# car.net
KiCad netlist of a schematic drawn in EAGLE
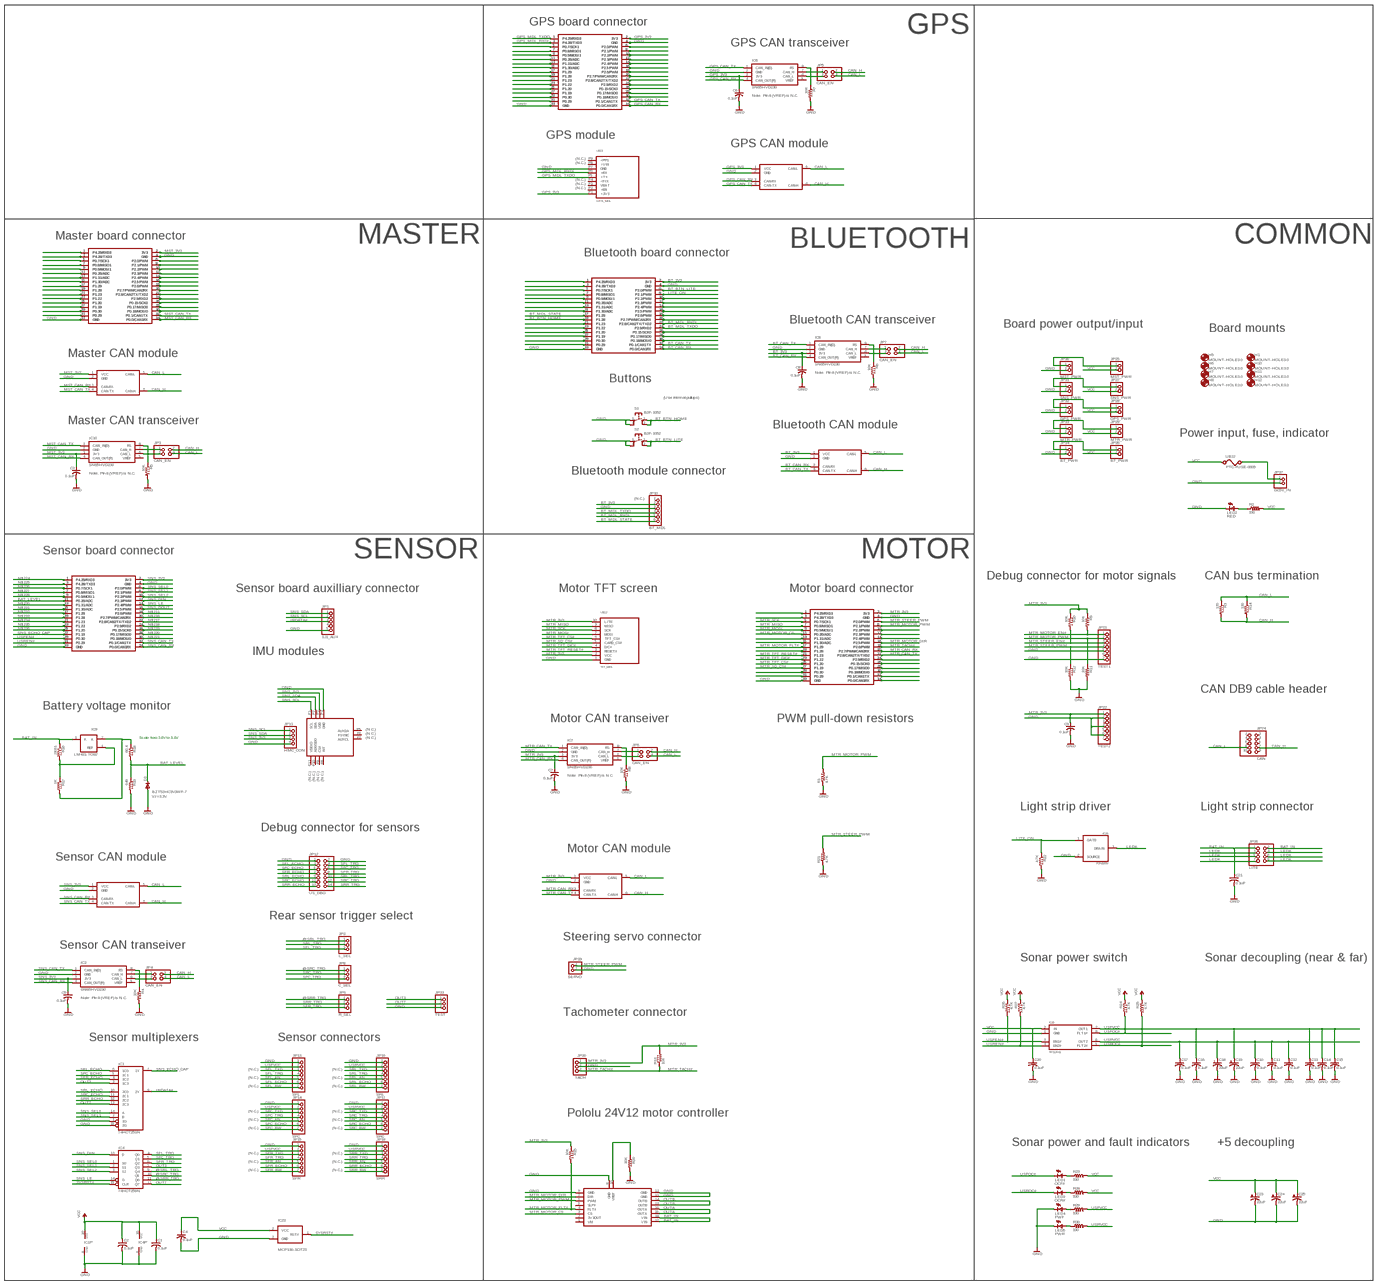
[diagram p0: schematic, sheet 1, overview]
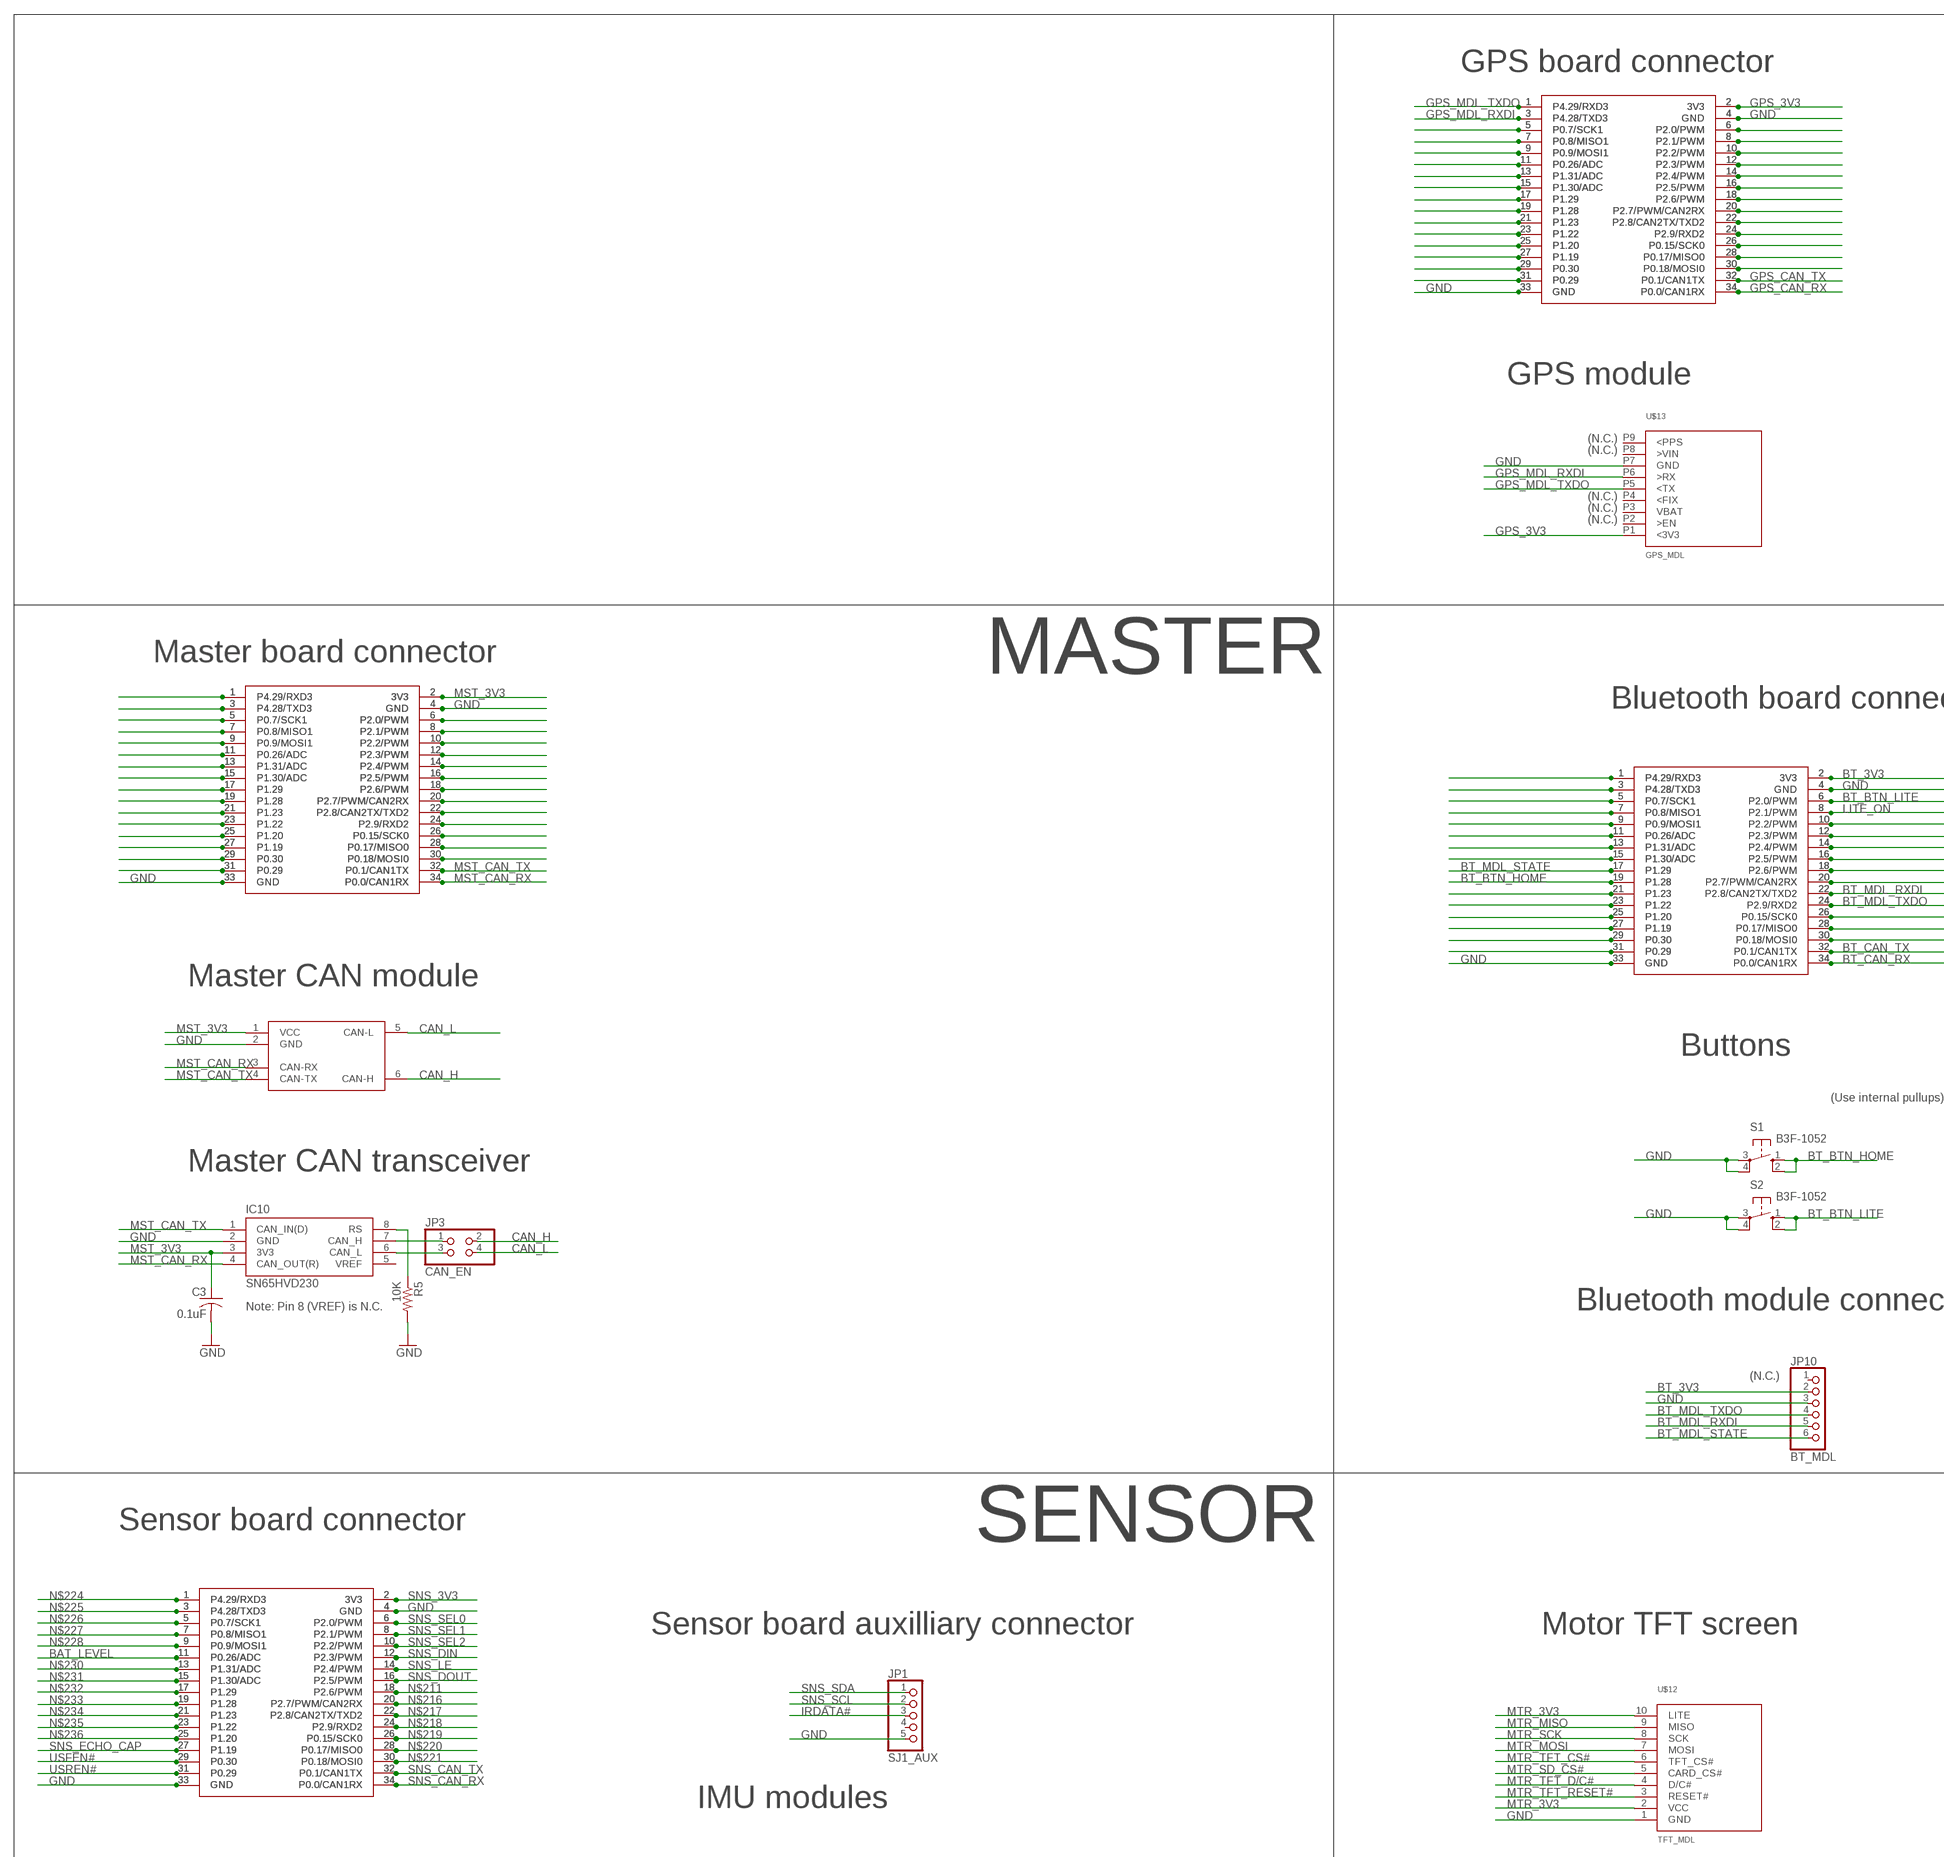
[diagram p1: schematic, sheet 1, part 1 of 4]
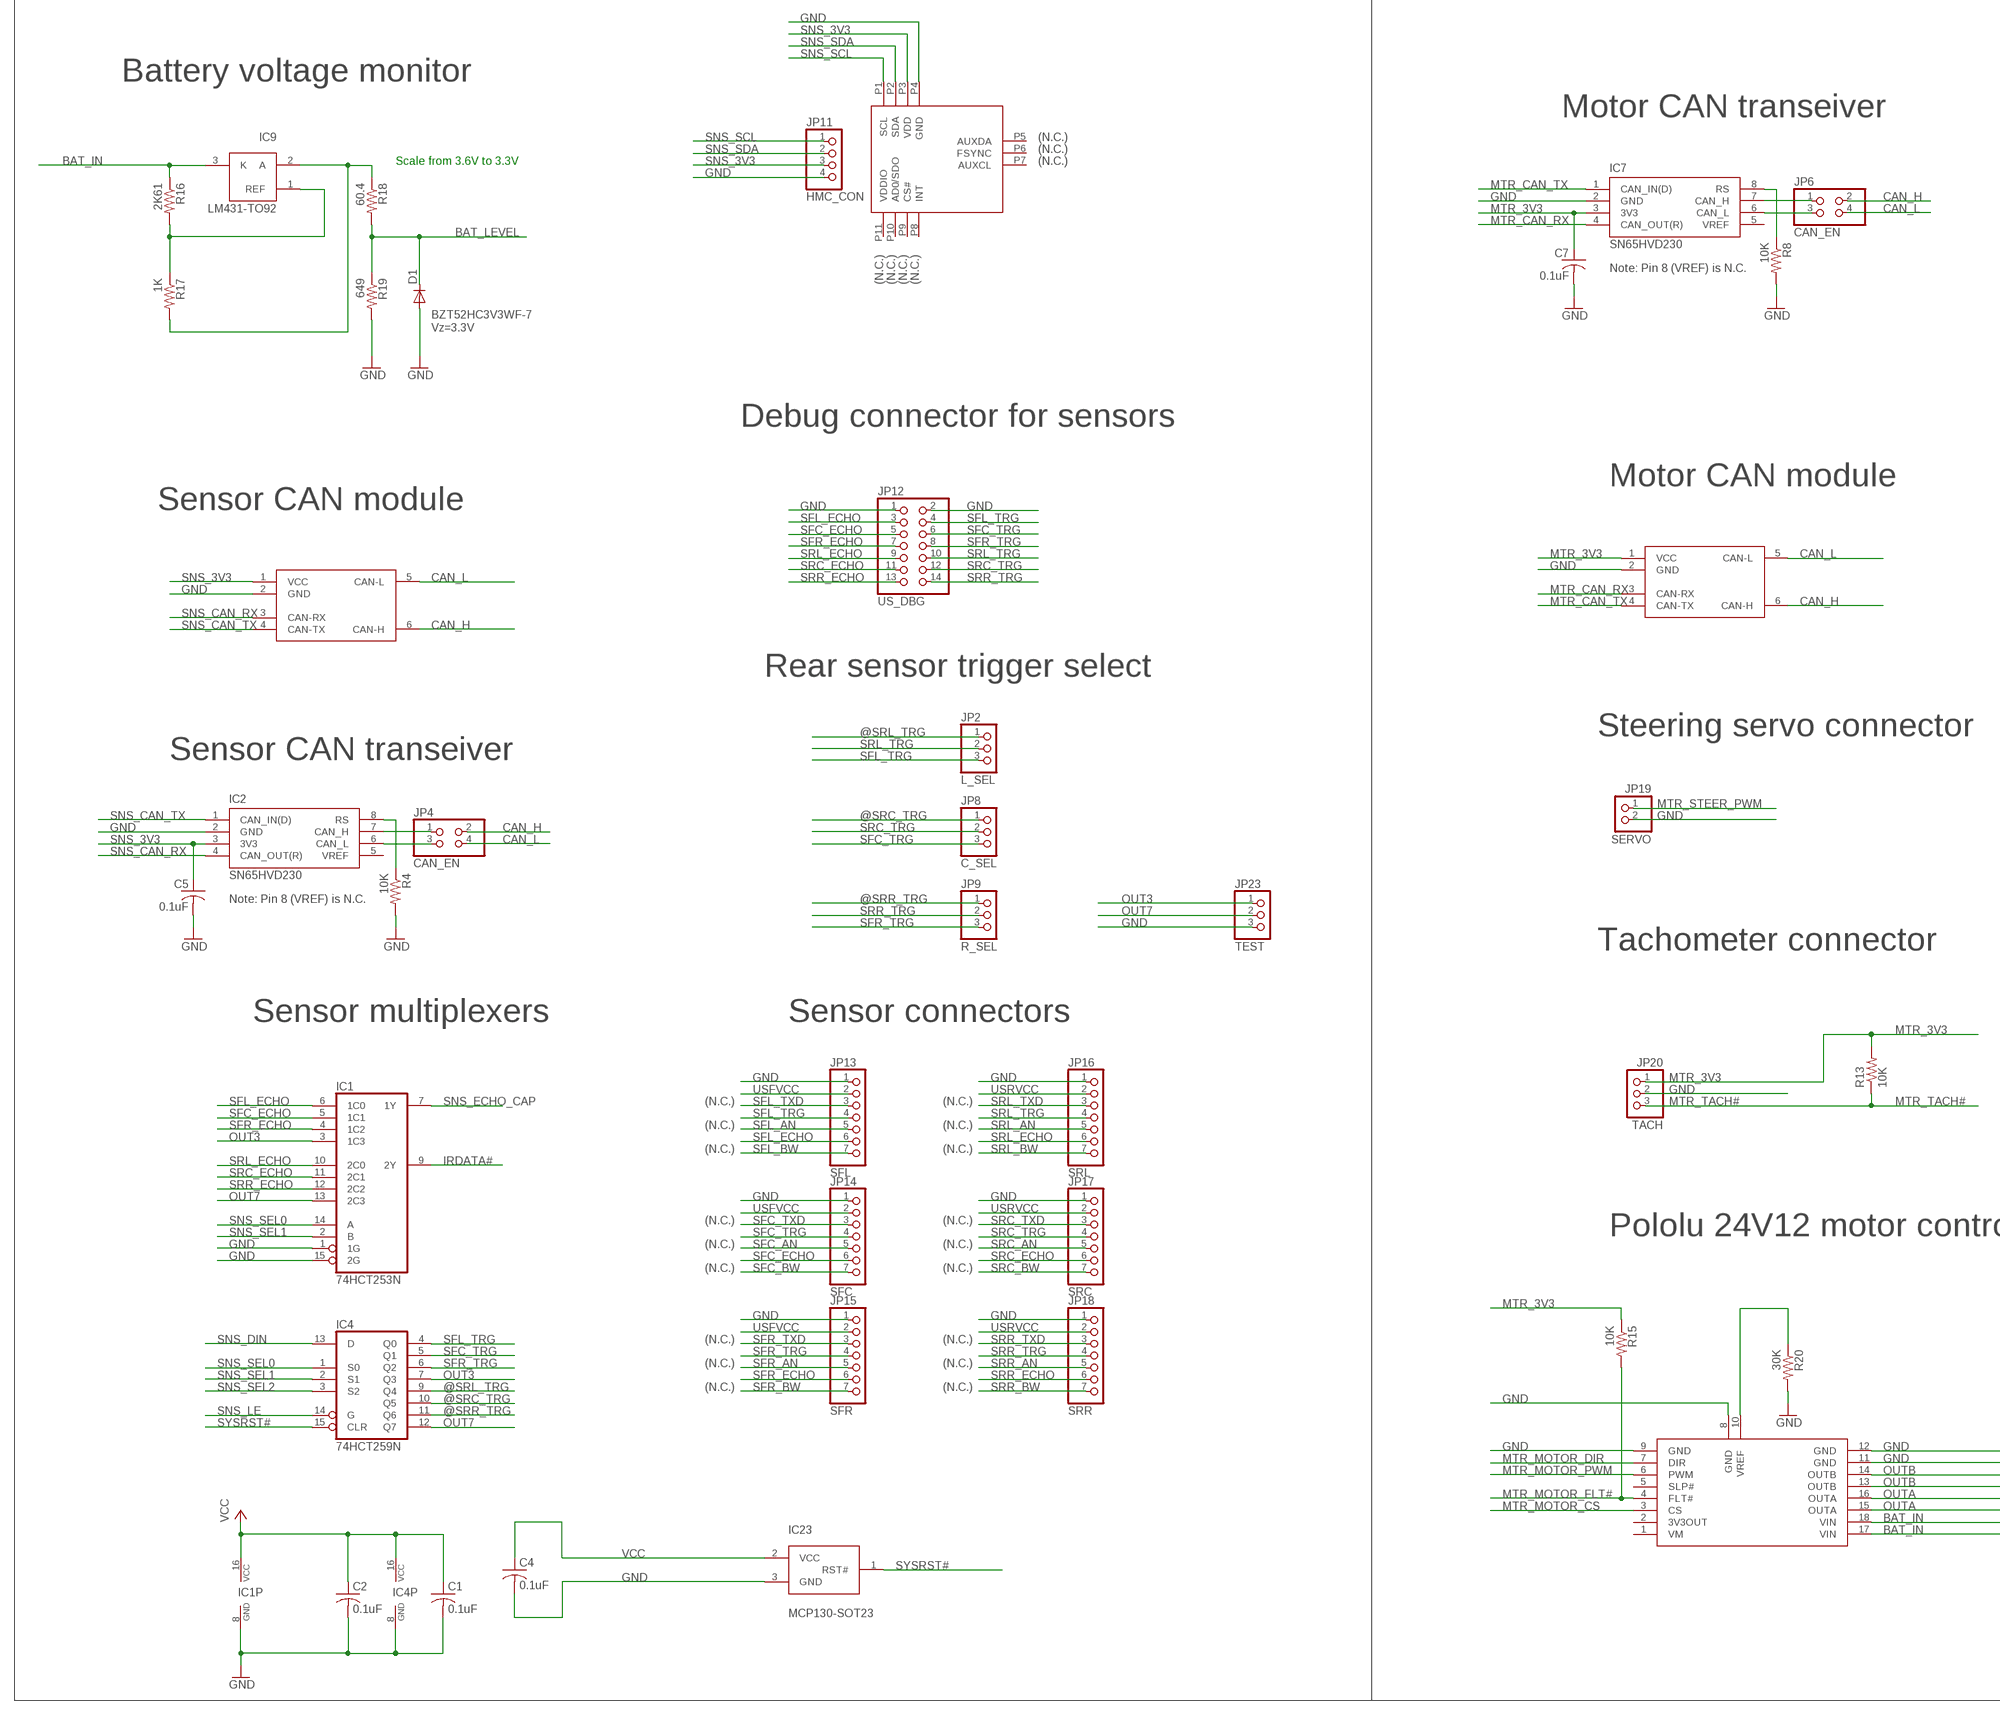
[diagram p2: schematic, sheet 1, part 2 of 4]
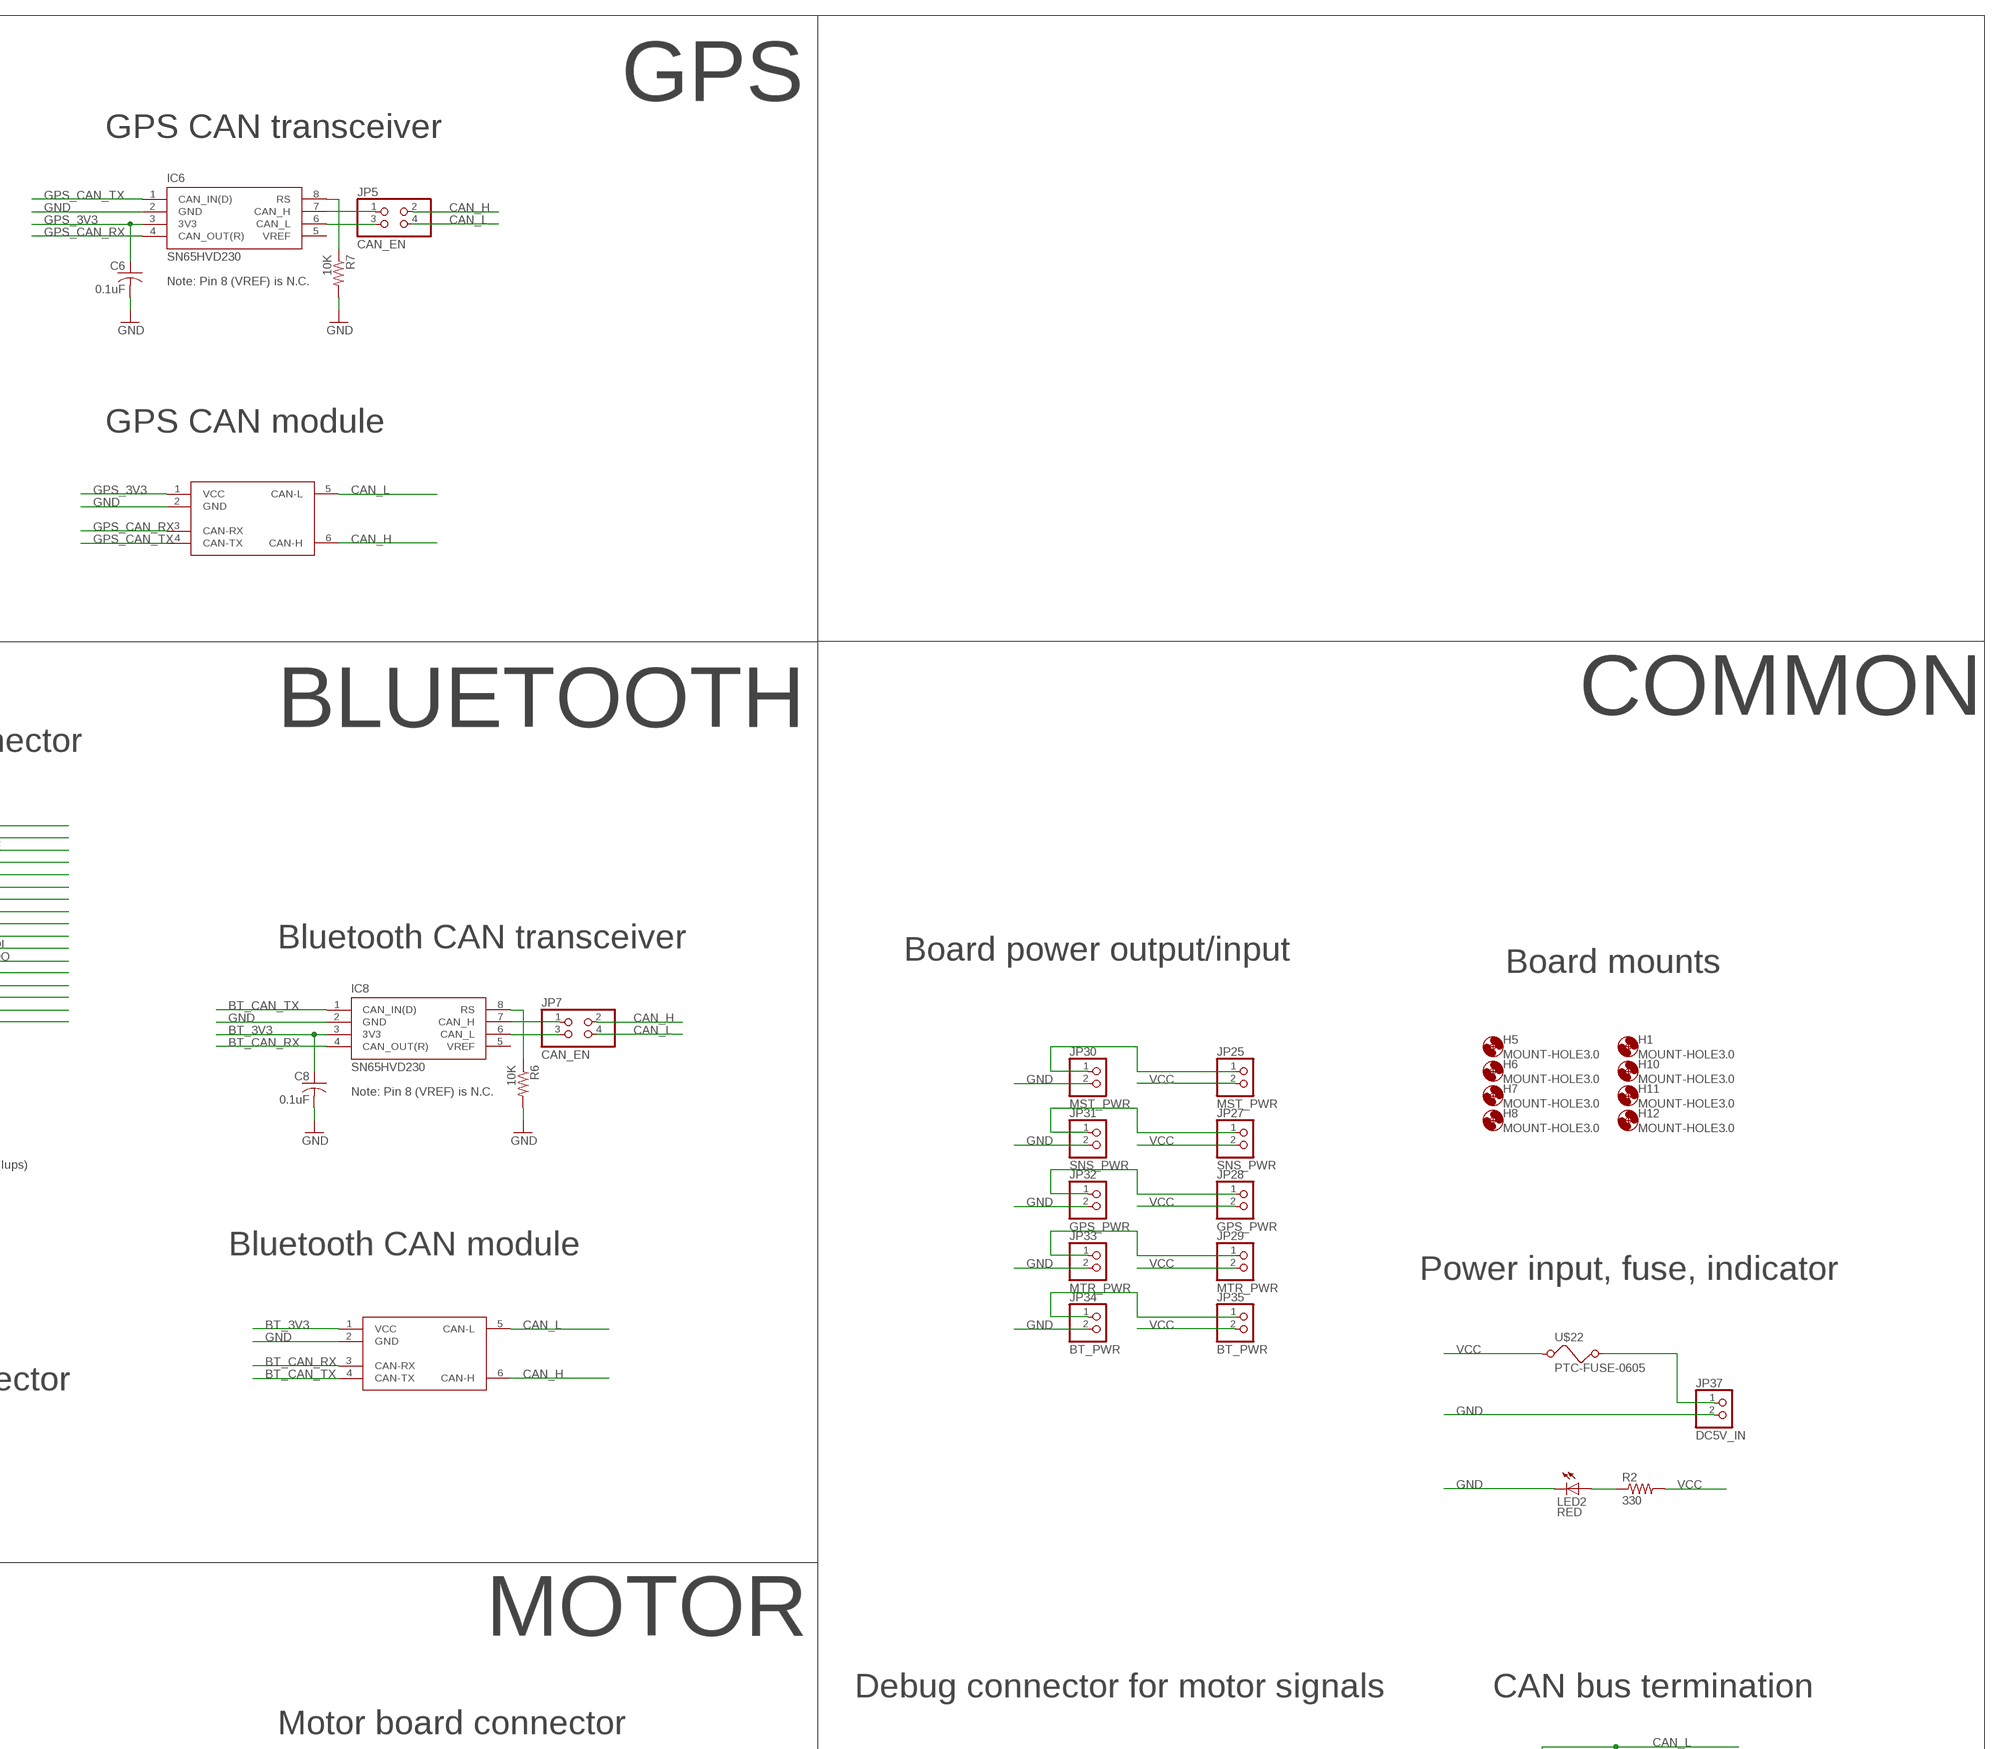
[diagram p3: schematic, sheet 1, part 3 of 4]
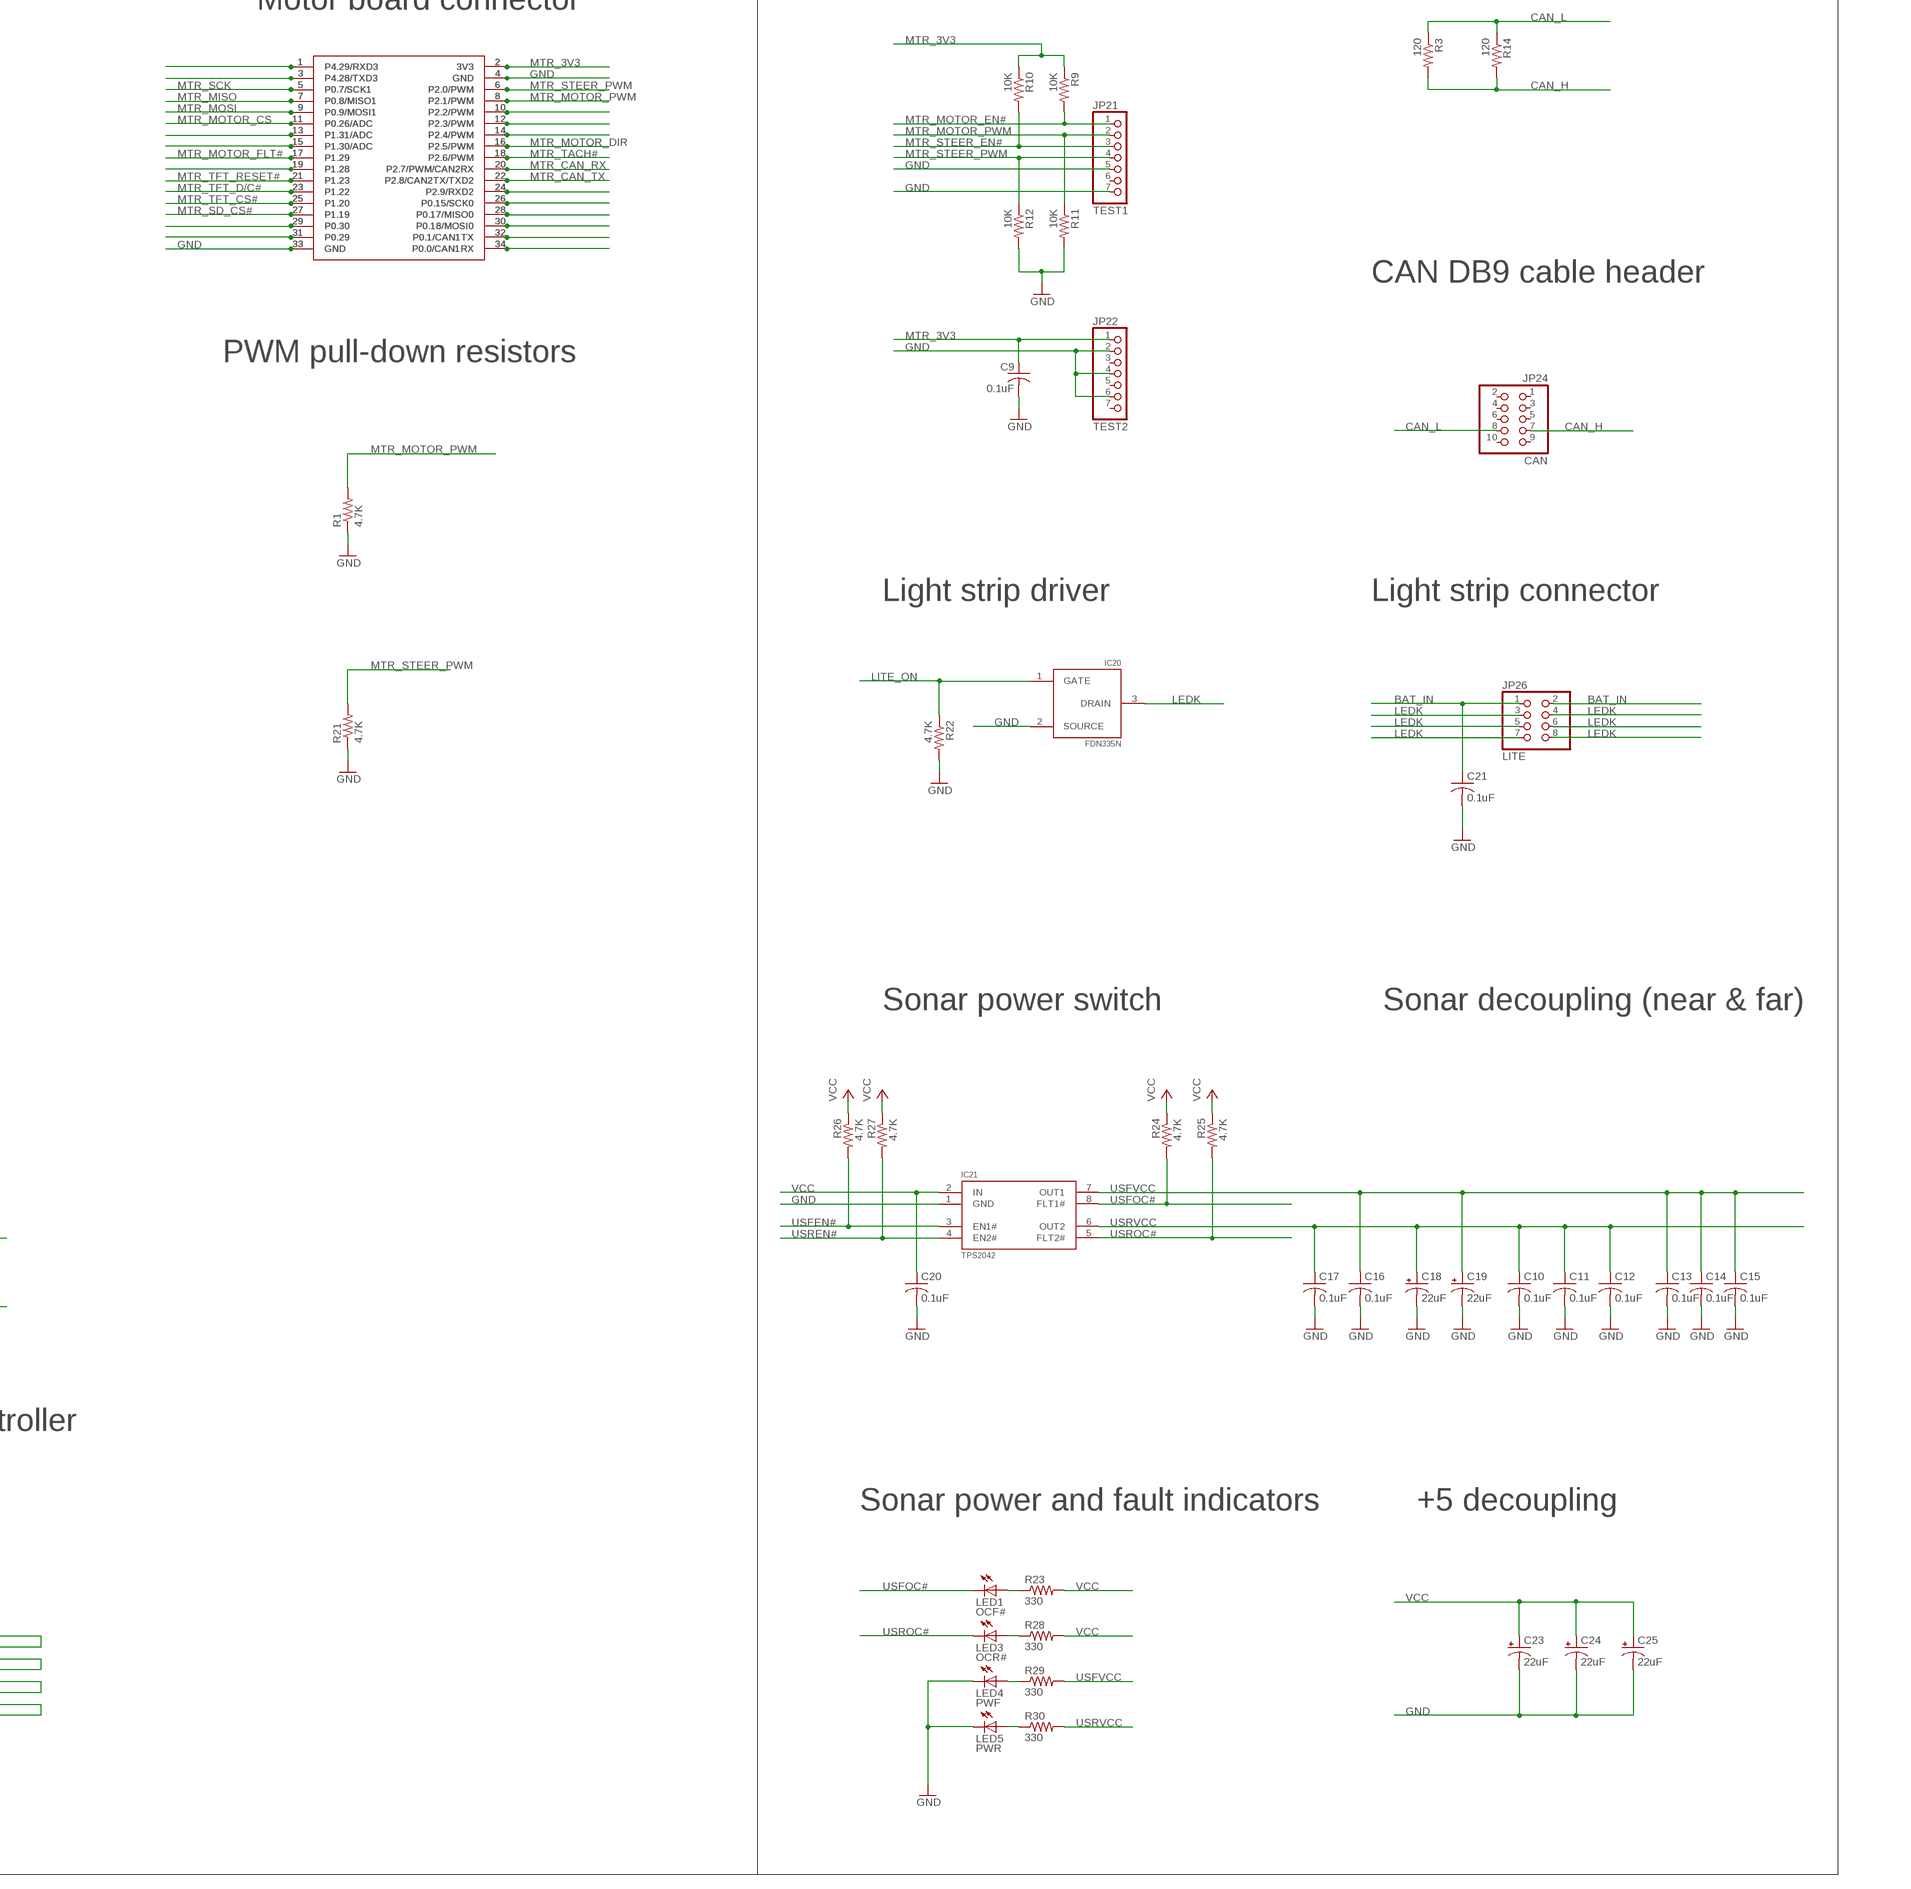
[diagram p4: schematic, sheet 1, part 4 of 4]

(export (version "E")
  (design (tool "Eeschema 10.0.6"))
  (components
    (comp (ref "C1")
      (value "0.1uF")
      (footprint "eagle-import:C0603K")
      (libsource (lib "eagle-import") (part "C-USC0603K"))
    )
    (comp (ref "C2")
      (value "0.1uF")
      (footprint "eagle-import:C0603K")
      (libsource (lib "eagle-import") (part "C-USC0603K"))
    )
    (comp (ref "C3")
      (value "0.1uF")
      (footprint "eagle-import:C0603K")
      (libsource (lib "eagle-import") (part "C-USC0603K"))
    )
    (comp (ref "C4")
      (value "0.1uF")
      (footprint "eagle-import:C0603K")
      (libsource (lib "eagle-import") (part "C-USC0603K"))
    )
    (comp (ref "C5")
      (value "0.1uF")
      (footprint "eagle-import:C0603K")
      (libsource (lib "eagle-import") (part "C-USC0603K"))
    )
    (comp (ref "C6")
      (value "0.1uF")
      (footprint "eagle-import:C0603K")
      (libsource (lib "eagle-import") (part "C-USC0603K"))
    )
    (comp (ref "C7")
      (value "0.1uF")
      (footprint "eagle-import:C0603K")
      (libsource (lib "eagle-import") (part "C-USC0603K"))
    )
    (comp (ref "C8")
      (value "0.1uF")
      (footprint "eagle-import:C0603K")
      (libsource (lib "eagle-import") (part "C-USC0603K"))
    )
    (comp (ref "C9")
      (value "0.1uF")
      (footprint "eagle-import:C0603K")
      (libsource (lib "eagle-import") (part "C-USC0603K"))
    )
    (comp (ref "C10")
      (value "0.1uF")
      (footprint "eagle-import:C0603K")
      (libsource (lib "eagle-import") (part "C-USC0603K"))
    )
    (comp (ref "C11")
      (value "0.1uF")
      (footprint "eagle-import:C0603K")
      (libsource (lib "eagle-import") (part "C-USC0603K"))
    )
    (comp (ref "C12")
      (value "0.1uF")
      (footprint "eagle-import:C0603K")
      (libsource (lib "eagle-import") (part "C-USC0603K"))
    )
    (comp (ref "C13")
      (value "0.1uF")
      (footprint "eagle-import:C0603K")
      (libsource (lib "eagle-import") (part "C-USC0603K"))
    )
    (comp (ref "C14")
      (value "0.1uF")
      (footprint "eagle-import:C0603K")
      (libsource (lib "eagle-import") (part "C-USC0603K"))
    )
    (comp (ref "C15")
      (value "0.1uF")
      (footprint "eagle-import:C0603K")
      (libsource (lib "eagle-import") (part "C-USC0603K"))
    )
    (comp (ref "C16")
      (value "0.1uF")
      (footprint "eagle-import:C0603K")
      (libsource (lib "eagle-import") (part "C-USC0603K"))
    )
    (comp (ref "C17")
      (value "0.1uF")
      (footprint "eagle-import:C0603K")
      (libsource (lib "eagle-import") (part "C-USC0603K"))
    )
    (comp (ref "C18")
      (value "22uF")
      (footprint "eagle-import:D_7343-31W")
      (libsource (lib "eagle-import") (part "CPOL-USD/7343-31W"))
    )
    (comp (ref "C19")
      (value "22uF")
      (footprint "eagle-import:D_7343-31W")
      (libsource (lib "eagle-import") (part "CPOL-USD/7343-31W"))
    )
    (comp (ref "C20")
      (value "0.1uF")
      (footprint "eagle-import:C0603K")
      (libsource (lib "eagle-import") (part "C-USC0603K"))
    )
    (comp (ref "C21")
      (value "0.1uF")
      (footprint "eagle-import:C0603K")
      (libsource (lib "eagle-import") (part "C-USC0603K"))
    )
    (comp (ref "C23")
      (value "22uF")
      (footprint "eagle-import:D_7343-31W")
      (libsource (lib "eagle-import") (part "CPOL-USD/7343-31W"))
    )
    (comp (ref "C24")
      (value "22uF")
      (footprint "eagle-import:D_7343-31W")
      (libsource (lib "eagle-import") (part "CPOL-USD/7343-31W"))
    )
    (comp (ref "C25")
      (value "22uF")
      (footprint "eagle-import:D_7343-31W")
      (libsource (lib "eagle-import") (part "CPOL-USD/7343-31W"))
    )
    (comp (ref "D1")
      (value "BZT52HC3V3WF-7")
      (footprint "eagle-import:SOD323-W")
      (libsource (lib "eagle-import") (part "DIODE-SOD323-W"))
    )
    (comp (ref "H1")
      (value "MOUNT-HOLE3.0")
      (footprint "eagle-import:3,0")
      (libsource (lib "eagle-import") (part "MOUNT-HOLE3.0"))
    )
    (comp (ref "H5")
      (value "MOUNT-HOLE3.0")
      (footprint "eagle-import:3,0")
      (libsource (lib "eagle-import") (part "MOUNT-HOLE3.0"))
    )
    (comp (ref "H6")
      (value "MOUNT-HOLE3.0")
      (footprint "eagle-import:3,0")
      (libsource (lib "eagle-import") (part "MOUNT-HOLE3.0"))
    )
    (comp (ref "H7")
      (value "MOUNT-HOLE3.0")
      (footprint "eagle-import:3,0")
      (libsource (lib "eagle-import") (part "MOUNT-HOLE3.0"))
    )
    (comp (ref "H8")
      (value "MOUNT-HOLE3.0")
      (footprint "eagle-import:3,0")
      (libsource (lib "eagle-import") (part "MOUNT-HOLE3.0"))
    )
    (comp (ref "H10")
      (value "MOUNT-HOLE3.0")
      (footprint "eagle-import:3,0")
      (libsource (lib "eagle-import") (part "MOUNT-HOLE3.0"))
    )
    (comp (ref "H11")
      (value "MOUNT-HOLE3.0")
      (footprint "eagle-import:3,0")
      (libsource (lib "eagle-import") (part "MOUNT-HOLE3.0"))
    )
    (comp (ref "H12")
      (value "MOUNT-HOLE3.0")
      (footprint "eagle-import:3,0")
      (libsource (lib "eagle-import") (part "MOUNT-HOLE3.0"))
    )
    (comp (ref "IC1")
      (value "74HCT253N")
      (footprint "eagle-import:DIL16")
      (libsource (lib "eagle-import") (part "74253NHCT"))
    )
    (comp (ref "IC2")
      (value "SN65HVD230")
      (footprint "eagle-import:SOIC8")
      (libsource (lib "eagle-import") (part "SN65HVD230"))
    )
    (comp (ref "IC4")
      (value "74HCT259N")
      (footprint "eagle-import:DIL16")
      (libsource (lib "eagle-import") (part "74259NHCT"))
    )
    (comp (ref "IC6")
      (value "SN65HVD230")
      (footprint "eagle-import:SOIC8")
      (libsource (lib "eagle-import") (part "SN65HVD230"))
    )
    (comp (ref "IC7")
      (value "SN65HVD230")
      (footprint "eagle-import:SOIC8")
      (libsource (lib "eagle-import") (part "SN65HVD230"))
    )
    (comp (ref "IC8")
      (value "SN65HVD230")
      (footprint "eagle-import:SOIC8")
      (libsource (lib "eagle-import") (part "SN65HVD230"))
    )
    (comp (ref "IC9")
      (value "LM431-TO92")
      (footprint "eagle-import:TO-92")
      (libsource (lib "eagle-import") (part "LM431-TO92"))
    )
    (comp (ref "IC10")
      (value "SN65HVD230")
      (footprint "eagle-import:SOIC8")
      (libsource (lib "eagle-import") (part "SN65HVD230"))
    )
    (comp (ref "IC20")
      (value "FDN335N")
      (footprint "eagle-import:SOT23-3")
      (libsource (lib "eagle-import") (part "FDN335N"))
    )
    (comp (ref "IC21")
      (value "TPS2042")
      (footprint "eagle-import:SOIC8")
      (libsource (lib "eagle-import") (part "TPS2042"))
    )
    (comp (ref "IC22")
      (value "24V21")
      (footprint "eagle-import:24V21")
      (libsource (lib "eagle-import") (part "24V21"))
    )
    (comp (ref "IC23")
      (value "MCP130-SOT23")
      (footprint "eagle-import:SOT23-3")
      (libsource (lib "eagle-import") (part "MCP130-SOT23"))
    )
    (comp (ref "IMU_MDL")
      (value "MPU9250")
      (footprint "eagle-import:MPU9250")
      (libsource (lib "eagle-import") (part "MPU9250"))
    )
    (comp (ref "JP1")
      (value "SJ1_AUX")
      (footprint "eagle-import:1X05")
      (libsource (lib "eagle-import") (part "PINHD-1X5"))
    )
    (comp (ref "JP2")
      (value "L_SEL")
      (footprint "eagle-import:1X03")
      (libsource (lib "eagle-import") (part "PINHD-1X3"))
    )
    (comp (ref "JP3")
      (value "CAN_EN")
      (footprint "eagle-import:2X02")
      (libsource (lib "eagle-import") (part "PINHD-2X2"))
    )
    (comp (ref "JP4")
      (value "CAN_EN")
      (footprint "eagle-import:2X02")
      (libsource (lib "eagle-import") (part "PINHD-2X2"))
    )
    (comp (ref "JP5")
      (value "CAN_EN")
      (footprint "eagle-import:2X02")
      (libsource (lib "eagle-import") (part "PINHD-2X2"))
    )
    (comp (ref "JP6")
      (value "CAN_EN")
      (footprint "eagle-import:2X02")
      (libsource (lib "eagle-import") (part "PINHD-2X2"))
    )
    (comp (ref "JP7")
      (value "CAN_EN")
      (footprint "eagle-import:2X02")
      (libsource (lib "eagle-import") (part "PINHD-2X2"))
    )
    (comp (ref "JP8")
      (value "C_SEL")
      (footprint "eagle-import:1X03")
      (libsource (lib "eagle-import") (part "PINHD-1X3"))
    )
    (comp (ref "JP9")
      (value "R_SEL")
      (footprint "eagle-import:1X03")
      (libsource (lib "eagle-import") (part "PINHD-1X3"))
    )
    (comp (ref "JP10")
      (value "BT_MDL")
      (footprint "eagle-import:1X06")
      (libsource (lib "eagle-import") (part "PINHD-1X6"))
    )
    (comp (ref "JP11")
      (value "HMC_CON")
      (footprint "eagle-import:1X04")
      (libsource (lib "eagle-import") (part "PINHD-1X4"))
    )
    (comp (ref "JP12")
      (value "US_DBG")
      (footprint "eagle-import:2X07")
      (libsource (lib "eagle-import") (part "PINHD-2X7"))
    )
    (comp (ref "JP13")
      (value "SFL")
      (footprint "eagle-import:1X07")
      (libsource (lib "eagle-import") (part "PINHD-1X7"))
    )
    (comp (ref "JP14")
      (value "SFC")
      (footprint "eagle-import:1X07")
      (libsource (lib "eagle-import") (part "PINHD-1X7"))
    )
    (comp (ref "JP15")
      (value "SFR")
      (footprint "eagle-import:1X07")
      (libsource (lib "eagle-import") (part "PINHD-1X7"))
    )
    (comp (ref "JP16")
      (value "SRL")
      (footprint "eagle-import:1X07")
      (libsource (lib "eagle-import") (part "PINHD-1X7"))
    )
    (comp (ref "JP17")
      (value "SRC")
      (footprint "eagle-import:1X07")
      (libsource (lib "eagle-import") (part "PINHD-1X7"))
    )
    (comp (ref "JP18")
      (value "SRR")
      (footprint "eagle-import:1X07")
      (libsource (lib "eagle-import") (part "PINHD-1X7"))
    )
    (comp (ref "JP19")
      (value "SERVO")
      (footprint "eagle-import:1X02")
      (libsource (lib "eagle-import") (part "PINHD-1X2"))
    )
    (comp (ref "JP20")
      (value "TACH")
      (footprint "eagle-import:1X03")
      (libsource (lib "eagle-import") (part "PINHD-1X3"))
    )
    (comp (ref "JP21")
      (value "TEST1")
      (footprint "eagle-import:1X07")
      (libsource (lib "eagle-import") (part "PINHD-1X7"))
    )
    (comp (ref "JP22")
      (value "TEST2")
      (footprint "eagle-import:1X07")
      (libsource (lib "eagle-import") (part "PINHD-1X7"))
    )
    (comp (ref "JP23")
      (value "TEST")
      (footprint "eagle-import:1X03")
      (libsource (lib "eagle-import") (part "PINHD-1X3"))
    )
    (comp (ref "JP24")
      (value "CAN")
      (footprint "eagle-import:2X05")
      (libsource (lib "eagle-import") (part "PINHD-2X5"))
    )
    (comp (ref "JP25")
      (value "MST_PWR")
      (footprint "eagle-import:1X02")
      (libsource (lib "eagle-import") (part "PINHD-1X2"))
    )
    (comp (ref "JP26")
      (value "LITE")
      (footprint "eagle-import:2X04")
      (libsource (lib "eagle-import") (part "PINHD-2X4"))
    )
    (comp (ref "JP27")
      (value "SNS_PWR")
      (footprint "eagle-import:1X02")
      (libsource (lib "eagle-import") (part "PINHD-1X2"))
    )
    (comp (ref "JP28")
      (value "GPS_PWR")
      (footprint "eagle-import:1X02")
      (libsource (lib "eagle-import") (part "PINHD-1X2"))
    )
    (comp (ref "JP29")
      (value "MTR_PWR")
      (footprint "eagle-import:1X02")
      (libsource (lib "eagle-import") (part "PINHD-1X2"))
    )
    (comp (ref "JP30")
      (value "MST_PWR")
      (footprint "eagle-import:1X02")
      (libsource (lib "eagle-import") (part "PINHD-1X2"))
    )
    (comp (ref "JP31")
      (value "SNS_PWR")
      (footprint "eagle-import:1X02")
      (libsource (lib "eagle-import") (part "PINHD-1X2"))
    )
    (comp (ref "JP32")
      (value "GPS_PWR")
      (footprint "eagle-import:1X02")
      (libsource (lib "eagle-import") (part "PINHD-1X2"))
    )
    (comp (ref "JP33")
      (value "MTR_PWR")
      (footprint "eagle-import:1X02")
      (libsource (lib "eagle-import") (part "PINHD-1X2"))
    )
    (comp (ref "JP34")
      (value "BT_PWR")
      (footprint "eagle-import:1X02")
      (libsource (lib "eagle-import") (part "PINHD-1X2"))
    )
    (comp (ref "JP35")
      (value "BT_PWR")
      (footprint "eagle-import:1X02")
      (libsource (lib "eagle-import") (part "PINHD-1X2"))
    )
    (comp (ref "JP37")
      (value "DC5V_IN")
      (footprint "eagle-import:1X02")
      (libsource (lib "eagle-import") (part "PINHD-1X2"))
    )
    (comp (ref "LED1")
      (value "OCF#")
      (footprint "eagle-import:CHIPLED_0603")
      (libsource (lib "eagle-import") (part "LEDCHIPLED_0603"))
    )
    (comp (ref "LED2")
      (value "RED")
      (footprint "eagle-import:CHIPLED_0603")
      (libsource (lib "eagle-import") (part "LEDCHIPLED_0603"))
    )
    (comp (ref "LED3")
      (value "OCR#")
      (footprint "eagle-import:CHIPLED_0603")
      (libsource (lib "eagle-import") (part "LEDCHIPLED_0603"))
    )
    (comp (ref "LED4")
      (value "PWF")
      (footprint "eagle-import:CHIPLED_0603")
      (libsource (lib "eagle-import") (part "LEDCHIPLED_0603"))
    )
    (comp (ref "LED5")
      (value "PWR")
      (footprint "eagle-import:CHIPLED_0603")
      (libsource (lib "eagle-import") (part "LEDCHIPLED_0603"))
    )
    (comp (ref "R1")
      (value "4.7K")
      (footprint "eagle-import:R0603")
      (libsource (lib "eagle-import") (part "R-US_R0603"))
    )
    (comp (ref "R2")
      (value "330")
      (footprint "eagle-import:R0603")
      (libsource (lib "eagle-import") (part "R-US_R0603"))
    )
    (comp (ref "R3")
      (value "120")
      (footprint "eagle-import:R0603")
      (libsource (lib "eagle-import") (part "R-US_R0603"))
    )
    (comp (ref "R4")
      (value "10K")
      (footprint "eagle-import:R0603")
      (libsource (lib "eagle-import") (part "R-US_R0603"))
    )
    (comp (ref "R5")
      (value "10K")
      (footprint "eagle-import:R0603")
      (libsource (lib "eagle-import") (part "R-US_R0603"))
    )
    (comp (ref "R6")
      (value "10K")
      (footprint "eagle-import:R0603")
      (libsource (lib "eagle-import") (part "R-US_R0603"))
    )
    (comp (ref "R7")
      (value "10K")
      (footprint "eagle-import:R0603")
      (libsource (lib "eagle-import") (part "R-US_R0603"))
    )
    (comp (ref "R8")
      (value "10K")
      (footprint "eagle-import:R0603")
      (libsource (lib "eagle-import") (part "R-US_R0603"))
    )
    (comp (ref "R9")
      (value "10K")
      (footprint "eagle-import:R0603")
      (libsource (lib "eagle-import") (part "R-US_R0603"))
    )
    (comp (ref "R10")
      (value "10K")
      (footprint "eagle-import:R0603")
      (libsource (lib "eagle-import") (part "R-US_R0603"))
    )
    (comp (ref "R11")
      (value "10K")
      (footprint "eagle-import:R0603")
      (libsource (lib "eagle-import") (part "R-US_R0603"))
    )
    (comp (ref "R12")
      (value "10K")
      (footprint "eagle-import:R0603")
      (libsource (lib "eagle-import") (part "R-US_R0603"))
    )
    (comp (ref "R13")
      (value "10K")
      (footprint "eagle-import:R0603")
      (libsource (lib "eagle-import") (part "R-US_R0603"))
    )
    (comp (ref "R14")
      (value "120")
      (footprint "eagle-import:R0603")
      (libsource (lib "eagle-import") (part "R-US_R0603"))
    )
    (comp (ref "R15")
      (value "10K")
      (footprint "eagle-import:R0603")
      (libsource (lib "eagle-import") (part "R-US_R0603"))
    )
    (comp (ref "R16")
      (value "2K61")
      (footprint "eagle-import:R0603")
      (libsource (lib "eagle-import") (part "R-US_R0603"))
    )
    (comp (ref "R17")
      (value "1K")
      (footprint "eagle-import:R0603")
      (libsource (lib "eagle-import") (part "R-US_R0603"))
    )
    (comp (ref "R18")
      (value "60.4")
      (footprint "eagle-import:R0603")
      (libsource (lib "eagle-import") (part "R-US_R0603"))
    )
    (comp (ref "R19")
      (value "649")
      (footprint "eagle-import:R0603")
      (libsource (lib "eagle-import") (part "R-US_R0603"))
    )
    (comp (ref "R20")
      (value "30K")
      (footprint "eagle-import:R0603")
      (libsource (lib "eagle-import") (part "R-US_R0603"))
    )
    (comp (ref "R21")
      (value "4.7K")
      (footprint "eagle-import:R0603")
      (libsource (lib "eagle-import") (part "R-US_R0603"))
    )
    (comp (ref "R22")
      (value "4.7K")
      (footprint "eagle-import:R0603")
      (libsource (lib "eagle-import") (part "R-US_R0603"))
    )
    (comp (ref "R23")
      (value "330")
      (footprint "eagle-import:R0603")
      (libsource (lib "eagle-import") (part "R-US_R0603"))
    )
    (comp (ref "R24")
      (value "4.7K")
      (footprint "eagle-import:R0603")
      (libsource (lib "eagle-import") (part "R-US_R0603"))
    )
    (comp (ref "R25")
      (value "4.7K")
      (footprint "eagle-import:R0603")
      (libsource (lib "eagle-import") (part "R-US_R0603"))
    )
    (comp (ref "R26")
      (value "4.7K")
      (footprint "eagle-import:R0603")
      (libsource (lib "eagle-import") (part "R-US_R0603"))
    )
    (comp (ref "R27")
      (value "4.7K")
      (footprint "eagle-import:R0603")
      (libsource (lib "eagle-import") (part "R-US_R0603"))
    )
    (comp (ref "R28")
      (value "330")
      (footprint "eagle-import:R0603")
      (libsource (lib "eagle-import") (part "R-US_R0603"))
    )
    (comp (ref "R29")
      (value "330")
      (footprint "eagle-import:R0603")
      (libsource (lib "eagle-import") (part "R-US_R0603"))
    )
    (comp (ref "R30")
      (value "330")
      (footprint "eagle-import:R0603")
      (libsource (lib "eagle-import") (part "R-US_R0603"))
    )
    (comp (ref "S1")
      (value "B3F-1052")
      (footprint "eagle-import:B3F-10XX")
      (fields (field (name "MPN") "B3F-1000"))
      (libsource (lib "eagle-import") (part "10-XX"))
    )
    (comp (ref "S2")
      (value "B3F-1052")
      (footprint "eagle-import:B3F-10XX")
      (fields (field (name "MPN") "B3F-1000"))
      (libsource (lib "eagle-import") (part "10-XX"))
    )
    (comp (ref "U$7")
      (value "WAVESHARE-CAN")
      (footprint "eagle-import:WAVESHARE-CAN")
      (libsource (lib "eagle-import") (part "WAVESHARE-CAN"))
    )
    (comp (ref "U$8")
      (value "WAVESHARE-CAN")
      (footprint "eagle-import:WAVESHARE-CAN")
      (libsource (lib "eagle-import") (part "WAVESHARE-CAN"))
    )
    (comp (ref "U$9")
      (value "WAVESHARE-CAN")
      (footprint "eagle-import:WAVESHARE-CAN")
      (libsource (lib "eagle-import") (part "WAVESHARE-CAN"))
    )
    (comp (ref "U$10")
      (value "WAVESHARE-CAN")
      (footprint "eagle-import:WAVESHARE-CAN")
      (libsource (lib "eagle-import") (part "WAVESHARE-CAN"))
    )
    (comp (ref "U$11")
      (value "WAVESHARE-CAN")
      (footprint "eagle-import:WAVESHARE-CAN")
      (libsource (lib "eagle-import") (part "WAVESHARE-CAN"))
    )
    (comp (ref "U$12")
      (value "TFT_MDL")
      (footprint "eagle-import:ADA-TFT")
      (libsource (lib "eagle-import") (part "ADA-TFT"))
    )
    (comp (ref "U$13")
      (value "GPS_MDL")
      (footprint "eagle-import:ADA-GPS")
      (libsource (lib "eagle-import") (part "ADA-GPS"))
    )
    (comp (ref "U$19")
      (value "SJ1_CONN")
      (footprint "eagle-import:SJ1_CONN")
      (libsource (lib "eagle-import") (part "SJ1_CONN"))
    )
    (comp (ref "U$20")
      (value "SJ1_CONN")
      (footprint "eagle-import:SJ1_CONN")
      (libsource (lib "eagle-import") (part "SJ1_CONN"))
    )
    (comp (ref "U$22")
      (value "PTC-FUSE-0605")
      (footprint "eagle-import:R0605")
      (libsource (lib "eagle-import") (part "PTC-FUSE-0605"))
    )
    (comp (ref "U$23")
      (value "SJ1_CONN")
      (footprint "eagle-import:SJ1_CONN")
      (libsource (lib "eagle-import") (part "SJ1_CONN"))
    )
    (comp (ref "U$24")
      (value "SJ1_CONN")
      (footprint "eagle-import:SJ1_CONN")
      (libsource (lib "eagle-import") (part "SJ1_CONN"))
    )
    (comp (ref "U$25")
      (value "SJ1_CONN")
      (footprint "eagle-import:SJ1_CONN")
      (libsource (lib "eagle-import") (part "SJ1_CONN"))
    )
    (comp (ref "U$26")
      (value "SJ1_CONN")
      (footprint "eagle-import:SJ1_CONN")
      (libsource (lib "eagle-import") (part "SJ1_CONN"))
    )
    (comp (ref "U$27")
      (value "SJ1_CONN")
      (footprint "eagle-import:SJ1_CONN")
      (libsource (lib "eagle-import") (part "SJ1_CONN"))
    )
    (comp (ref "U$28")
      (value "SJ1_CONN")
      (footprint "eagle-import:SJ1_CONN")
      (libsource (lib "eagle-import") (part "SJ1_CONN"))
    )
    (comp (ref "U$29")
      (value "SJ1_CONN")
      (footprint "eagle-import:SJ1_CONN")
      (libsource (lib "eagle-import") (part "SJ1_CONN"))
    )
    (comp (ref "U$30")
      (value "SJ1_CONN")
      (footprint "eagle-import:SJ1_CONN")
      (libsource (lib "eagle-import") (part "SJ1_CONN"))
    )
  )
  (nets
    (net (code "1") (name "/@SRC_TRG") (class "Default")
      (node (ref "IC4") (pin "10") (pinfunction "Q5_10") (pintype "output"))
      (node (ref "JP8") (pin "1") (pinfunction "1_1") (pintype "passive"))
    )
    (net (code "2") (name "/@SRL_TRG") (class "Default")
      (node (ref "IC4") (pin "9") (pinfunction "Q4_9") (pintype "output"))
      (node (ref "JP2") (pin "1") (pinfunction "1_1") (pintype "passive"))
    )
    (net (code "3") (name "/@SRR_TRG") (class "Default")
      (node (ref "IC4") (pin "11") (pinfunction "Q6_11") (pintype "output"))
      (node (ref "JP9") (pin "1") (pinfunction "1_1") (pintype "passive"))
    )
    (net (code "4") (name "/BAT_IN") (class "Default")
      (node (ref "C21") (pin "1") (pinfunction "1_1") (pintype "passive"))
      (node (ref "IC22") (pin "17") (pinfunction "VIN_17") (pintype "bidirectional"))
      (node (ref "IC22") (pin "18") (pinfunction "VIN_18") (pintype "bidirectional"))
      (node (ref "IC9") (pin "3") (pinfunction "K_3") (pintype "bidirectional"))
      (node (ref "JP26") (pin "1") (pinfunction "1_1") (pintype "passive"))
      (node (ref "JP26") (pin "2") (pinfunction "2_2") (pintype "passive"))
      (node (ref "R16") (pin "1") (pinfunction "1_1") (pintype "passive"))
    )
    (net (code "5") (name "/BAT_LEVEL") (class "Default")
      (node (ref "D1") (pin "C") (pinfunction "C_C") (pintype "passive"))
      (node (ref "R18") (pin "2") (pinfunction "2_2") (pintype "passive"))
      (node (ref "R19") (pin "1") (pinfunction "1_1") (pintype "passive"))
      (node (ref "U$19") (pin "11") (pinfunction "P0.26/ADC_11") (pintype "bidirectional"))
      (node (ref "U$20") (pin "11") (pinfunction "P0.26/ADC_11") (pintype "bidirectional"))
    )
    (net (code "6") (name "/BT_3V3") (class "Default")
      (node (ref "C8") (pin "1") (pinfunction "1_1") (pintype "passive"))
      (node (ref "IC8") (pin "3") (pinfunction "3V3_3") (pintype "bidirectional"))
      (node (ref "JP10") (pin "2") (pinfunction "2_2") (pintype "passive"))
      (node (ref "U$27") (pin "2") (pinfunction "3V3_2") (pintype "bidirectional"))
      (node (ref "U$30") (pin "2") (pinfunction "3V3_2") (pintype "bidirectional"))
      (node (ref "U$8") (pin "1") (pinfunction "VCC_1") (pintype "bidirectional"))
    )
    (net (code "7") (name "/BT_BTN_HOME") (class "Default")
      (node (ref "S1") (pin "1") (pinfunction "S_1") (pintype "passive"))
      (node (ref "S1") (pin "2") (pinfunction "S1_2") (pintype "passive"))
      (node (ref "U$27") (pin "19") (pinfunction "P1.28_19") (pintype "bidirectional"))
      (node (ref "U$30") (pin "19") (pinfunction "P1.28_19") (pintype "bidirectional"))
    )
    (net (code "8") (name "/BT_BTN_LITE") (class "Default")
      (node (ref "S2") (pin "1") (pinfunction "S_1") (pintype "passive"))
      (node (ref "S2") (pin "2") (pinfunction "S1_2") (pintype "passive"))
      (node (ref "U$27") (pin "6") (pinfunction "P2.0/PWM_6") (pintype "bidirectional"))
      (node (ref "U$30") (pin "6") (pinfunction "P2.0/PWM_6") (pintype "bidirectional"))
    )
    (net (code "9") (name "/BT_CAN_RX") (class "Default")
      (node (ref "IC8") (pin "4") (pinfunction "CAN_OUT(R)_4") (pintype "bidirectional"))
      (node (ref "U$27") (pin "34") (pinfunction "P0.0/CAN1RX_34") (pintype "bidirectional"))
      (node (ref "U$30") (pin "34") (pinfunction "P0.0/CAN1RX_34") (pintype "bidirectional"))
      (node (ref "U$8") (pin "3") (pinfunction "CAN-RX_3") (pintype "bidirectional"))
    )
    (net (code "10") (name "/BT_CAN_TX") (class "Default")
      (node (ref "IC8") (pin "1") (pinfunction "CAN_IN(D)_1") (pintype "bidirectional"))
      (node (ref "U$27") (pin "32") (pinfunction "P0.1/CAN1TX_32") (pintype "bidirectional"))
      (node (ref "U$30") (pin "32") (pinfunction "P0.1/CAN1TX_32") (pintype "bidirectional"))
      (node (ref "U$8") (pin "4") (pinfunction "CAN-TX_4") (pintype "bidirectional"))
    )
    (net (code "11") (name "/BT_MDL_RXDI") (class "Default")
      (node (ref "JP10") (pin "5") (pinfunction "5_5") (pintype "passive"))
      (node (ref "U$27") (pin "22") (pinfunction "P2.8/CAN2TX/TXD2_22") (pintype "bidirectional"))
      (node (ref "U$30") (pin "22") (pinfunction "P2.8/CAN2TX/TXD2_22") (pintype "bidirectional"))
    )
    (net (code "12") (name "/BT_MDL_STATE") (class "Default")
      (node (ref "JP10") (pin "6") (pinfunction "6_6") (pintype "passive"))
      (node (ref "U$27") (pin "17") (pinfunction "P1.29_17") (pintype "bidirectional"))
      (node (ref "U$30") (pin "17") (pinfunction "P1.29_17") (pintype "bidirectional"))
    )
    (net (code "13") (name "/BT_MDL_TXDO") (class "Default")
      (node (ref "JP10") (pin "4") (pinfunction "4_4") (pintype "passive"))
      (node (ref "U$27") (pin "24") (pinfunction "P2.9/RXD2_24") (pintype "bidirectional"))
      (node (ref "U$30") (pin "24") (pinfunction "P2.9/RXD2_24") (pintype "bidirectional"))
    )
    (net (code "14") (name "/CAN_H") (class "Default")
      (node (ref "JP24") (pin "7") (pinfunction "7_7") (pintype "passive"))
      (node (ref "JP3") (pin "2") (pinfunction "2_2") (pintype "passive"))
      (node (ref "JP4") (pin "2") (pinfunction "2_2") (pintype "passive"))
      (node (ref "JP5") (pin "2") (pinfunction "2_2") (pintype "passive"))
      (node (ref "JP6") (pin "2") (pinfunction "2_2") (pintype "passive"))
      (node (ref "JP7") (pin "2") (pinfunction "2_2") (pintype "passive"))
      (node (ref "R14") (pin "2") (pinfunction "2_2") (pintype "passive"))
      (node (ref "R3") (pin "2") (pinfunction "2_2") (pintype "passive"))
      (node (ref "U$10") (pin "6") (pinfunction "CAN-H_6") (pintype "bidirectional"))
      (node (ref "U$11") (pin "6") (pinfunction "CAN-H_6") (pintype "bidirectional"))
      (node (ref "U$7") (pin "6") (pinfunction "CAN-H_6") (pintype "bidirectional"))
      (node (ref "U$8") (pin "6") (pinfunction "CAN-H_6") (pintype "bidirectional"))
      (node (ref "U$9") (pin "6") (pinfunction "CAN-H_6") (pintype "bidirectional"))
    )
    (net (code "15") (name "/CAN_L") (class "Default")
      (node (ref "JP24") (pin "8") (pinfunction "8_8") (pintype "passive"))
      (node (ref "JP3") (pin "4") (pinfunction "4_4") (pintype "passive"))
      (node (ref "JP4") (pin "4") (pinfunction "4_4") (pintype "passive"))
      (node (ref "JP5") (pin "4") (pinfunction "4_4") (pintype "passive"))
      (node (ref "JP6") (pin "4") (pinfunction "4_4") (pintype "passive"))
      (node (ref "JP7") (pin "4") (pinfunction "4_4") (pintype "passive"))
      (node (ref "R14") (pin "1") (pinfunction "1_1") (pintype "passive"))
      (node (ref "R3") (pin "1") (pinfunction "1_1") (pintype "passive"))
      (node (ref "U$10") (pin "5") (pinfunction "CAN-L_5") (pintype "bidirectional"))
      (node (ref "U$11") (pin "5") (pinfunction "CAN-L_5") (pintype "bidirectional"))
      (node (ref "U$7") (pin "5") (pinfunction "CAN-L_5") (pintype "bidirectional"))
      (node (ref "U$8") (pin "5") (pinfunction "CAN-L_5") (pintype "bidirectional"))
      (node (ref "U$9") (pin "5") (pinfunction "CAN-L_5") (pintype "bidirectional"))
    )
    (net (code "16") (name "/GPS_3V3") (class "Default")
      (node (ref "C6") (pin "1") (pinfunction "1_1") (pintype "passive"))
      (node (ref "IC6") (pin "3") (pinfunction "3V3_3") (pintype "bidirectional"))
      (node (ref "U$10") (pin "1") (pinfunction "VCC_1") (pintype "bidirectional"))
      (node (ref "U$13") (pin "P1") (pinfunction "<3V3_P1") (pintype "bidirectional"))
      (node (ref "U$28") (pin "2") (pinfunction "3V3_2") (pintype "bidirectional"))
      (node (ref "U$29") (pin "2") (pinfunction "3V3_2") (pintype "bidirectional"))
    )
    (net (code "17") (name "/GPS_CAN_RX") (class "Default")
      (node (ref "IC6") (pin "4") (pinfunction "CAN_OUT(R)_4") (pintype "bidirectional"))
      (node (ref "U$10") (pin "3") (pinfunction "CAN-RX_3") (pintype "bidirectional"))
      (node (ref "U$28") (pin "34") (pinfunction "P0.0/CAN1RX_34") (pintype "bidirectional"))
      (node (ref "U$29") (pin "34") (pinfunction "P0.0/CAN1RX_34") (pintype "bidirectional"))
    )
    (net (code "18") (name "/GPS_CAN_TX") (class "Default")
      (node (ref "IC6") (pin "1") (pinfunction "CAN_IN(D)_1") (pintype "bidirectional"))
      (node (ref "U$10") (pin "4") (pinfunction "CAN-TX_4") (pintype "bidirectional"))
      (node (ref "U$28") (pin "32") (pinfunction "P0.1/CAN1TX_32") (pintype "bidirectional"))
      (node (ref "U$29") (pin "32") (pinfunction "P0.1/CAN1TX_32") (pintype "bidirectional"))
    )
    (net (code "19") (name "/GPS_MDL_RXDI") (class "Default")
      (node (ref "U$13") (pin "P6") (pinfunction ">RX_P6") (pintype "bidirectional"))
      (node (ref "U$28") (pin "3") (pinfunction "P4.28/TXD3_3") (pintype "bidirectional"))
      (node (ref "U$29") (pin "3") (pinfunction "P4.28/TXD3_3") (pintype "bidirectional"))
    )
    (net (code "20") (name "/GPS_MDL_TXDO") (class "Default")
      (node (ref "U$13") (pin "P5") (pinfunction "<TX_P5") (pintype "bidirectional"))
      (node (ref "U$28") (pin "1") (pinfunction "P4.29/RXD3_1") (pintype "bidirectional"))
      (node (ref "U$29") (pin "1") (pinfunction "P4.29/RXD3_1") (pintype "bidirectional"))
    )
    (net (code "21") (name "/IRDATA#") (class "Default")
      (node (ref "IC1") (pin "9") (pinfunction "2Y_9") (pintype "tri_state"))
      (node (ref "JP1") (pin "3") (pinfunction "3_3") (pintype "passive"))
    )
    (net (code "22") (name "/LEDK") (class "Default")
      (node (ref "IC20") (pin "3") (pinfunction "DRAIN_3") (pintype "bidirectional"))
      (node (ref "JP26") (pin "3") (pinfunction "3_3") (pintype "passive"))
      (node (ref "JP26") (pin "4") (pinfunction "4_4") (pintype "passive"))
      (node (ref "JP26") (pin "5") (pinfunction "5_5") (pintype "passive"))
      (node (ref "JP26") (pin "6") (pinfunction "6_6") (pintype "passive"))
      (node (ref "JP26") (pin "7") (pinfunction "7_7") (pintype "passive"))
      (node (ref "JP26") (pin "8") (pinfunction "8_8") (pintype "passive"))
    )
    (net (code "23") (name "/LITE_ON") (class "Default")
      (node (ref "IC20") (pin "1") (pinfunction "GATE_1") (pintype "bidirectional"))
      (node (ref "R22") (pin "1") (pinfunction "1_1") (pintype "passive"))
      (node (ref "U$27") (pin "8") (pinfunction "P2.1/PWM_8") (pintype "bidirectional"))
      (node (ref "U$30") (pin "8") (pinfunction "P2.1/PWM_8") (pintype "bidirectional"))
    )
    (net (code "24") (name "/MST_3V3") (class "Default")
      (node (ref "C3") (pin "1") (pinfunction "1_1") (pintype "passive"))
      (node (ref "IC10") (pin "3") (pinfunction "3V3_3") (pintype "bidirectional"))
      (node (ref "U$23") (pin "2") (pinfunction "3V3_2") (pintype "bidirectional"))
      (node (ref "U$24") (pin "2") (pinfunction "3V3_2") (pintype "bidirectional"))
      (node (ref "U$7") (pin "1") (pinfunction "VCC_1") (pintype "bidirectional"))
    )
    (net (code "25") (name "/MST_CAN_RX") (class "Default")
      (node (ref "IC10") (pin "4") (pinfunction "CAN_OUT(R)_4") (pintype "bidirectional"))
      (node (ref "U$23") (pin "34") (pinfunction "P0.0/CAN1RX_34") (pintype "bidirectional"))
      (node (ref "U$24") (pin "34") (pinfunction "P0.0/CAN1RX_34") (pintype "bidirectional"))
      (node (ref "U$7") (pin "3") (pinfunction "CAN-RX_3") (pintype "bidirectional"))
    )
    (net (code "26") (name "/MST_CAN_TX") (class "Default")
      (node (ref "IC10") (pin "1") (pinfunction "CAN_IN(D)_1") (pintype "bidirectional"))
      (node (ref "U$23") (pin "32") (pinfunction "P0.1/CAN1TX_32") (pintype "bidirectional"))
      (node (ref "U$24") (pin "32") (pinfunction "P0.1/CAN1TX_32") (pintype "bidirectional"))
      (node (ref "U$7") (pin "4") (pinfunction "CAN-TX_4") (pintype "bidirectional"))
    )
    (net (code "27") (name "/MTR_3V3") (class "Default")
      (node (ref "C7") (pin "1") (pinfunction "1_1") (pintype "passive"))
      (node (ref "C9") (pin "1") (pinfunction "1_1") (pintype "passive"))
      (node (ref "IC7") (pin "3") (pinfunction "3V3_3") (pintype "bidirectional"))
      (node (ref "JP20") (pin "1") (pinfunction "1_1") (pintype "passive"))
      (node (ref "JP22") (pin "1") (pinfunction "1_1") (pintype "passive"))
      (node (ref "R10") (pin "1") (pinfunction "1_1") (pintype "passive"))
      (node (ref "R13") (pin "2") (pinfunction "2_2") (pintype "passive"))
      (node (ref "R15") (pin "1") (pinfunction "1_1") (pintype "passive"))
      (node (ref "R9") (pin "1") (pinfunction "1_1") (pintype "passive"))
      (node (ref "U$11") (pin "1") (pinfunction "VCC_1") (pintype "bidirectional"))
      (node (ref "U$12") (pin "10") (pinfunction "LITE_10") (pintype "bidirectional"))
      (node (ref "U$12") (pin "2") (pinfunction "VCC_2") (pintype "bidirectional"))
      (node (ref "U$25") (pin "2") (pinfunction "3V3_2") (pintype "bidirectional"))
      (node (ref "U$26") (pin "2") (pinfunction "3V3_2") (pintype "bidirectional"))
    )
    (net (code "28") (name "/MTR_CAN_RX") (class "Default")
      (node (ref "IC7") (pin "4") (pinfunction "CAN_OUT(R)_4") (pintype "bidirectional"))
      (node (ref "U$11") (pin "3") (pinfunction "CAN-RX_3") (pintype "bidirectional"))
      (node (ref "U$25") (pin "20") (pinfunction "P2.7/PWM/CAN2RX_20") (pintype "bidirectional"))
      (node (ref "U$26") (pin "20") (pinfunction "P2.7/PWM/CAN2RX_20") (pintype "bidirectional"))
    )
    (net (code "29") (name "/MTR_CAN_TX") (class "Default")
      (node (ref "IC7") (pin "1") (pinfunction "CAN_IN(D)_1") (pintype "bidirectional"))
      (node (ref "U$11") (pin "4") (pinfunction "CAN-TX_4") (pintype "bidirectional"))
      (node (ref "U$25") (pin "22") (pinfunction "P2.8/CAN2TX/TXD2_22") (pintype "bidirectional"))
      (node (ref "U$26") (pin "22") (pinfunction "P2.8/CAN2TX/TXD2_22") (pintype "bidirectional"))
    )
    (net (code "30") (name "/MTR_MISO") (class "Default")
      (node (ref "U$12") (pin "9") (pinfunction "MISO_9") (pintype "bidirectional"))
      (node (ref "U$25") (pin "7") (pinfunction "P0.8/MISO1_7") (pintype "bidirectional"))
      (node (ref "U$26") (pin "7") (pinfunction "P0.8/MISO1_7") (pintype "bidirectional"))
    )
    (net (code "31") (name "/MTR_MOSI") (class "Default")
      (node (ref "U$12") (pin "7") (pinfunction "MOSI_7") (pintype "bidirectional"))
      (node (ref "U$25") (pin "9") (pinfunction "P0.9/MOSI1_9") (pintype "bidirectional"))
      (node (ref "U$26") (pin "9") (pinfunction "P0.9/MOSI1_9") (pintype "bidirectional"))
    )
    (net (code "32") (name "/MTR_MOTOR_CS") (class "Default")
      (node (ref "IC22") (pin "3") (pinfunction "CS_3") (pintype "bidirectional"))
      (node (ref "U$25") (pin "11") (pinfunction "P0.26/ADC_11") (pintype "bidirectional"))
      (node (ref "U$26") (pin "11") (pinfunction "P0.26/ADC_11") (pintype "bidirectional"))
    )
    (net (code "33") (name "/MTR_MOTOR_DIR") (class "Default")
      (node (ref "IC22") (pin "7") (pinfunction "DIR_7") (pintype "bidirectional"))
      (node (ref "U$25") (pin "16") (pinfunction "P2.5/PWM_16") (pintype "bidirectional"))
      (node (ref "U$26") (pin "16") (pinfunction "P2.5/PWM_16") (pintype "bidirectional"))
    )
    (net (code "34") (name "/MTR_MOTOR_EN#") (class "Default")
      (node (ref "JP21") (pin "1") (pinfunction "1_1") (pintype "passive"))
      (node (ref "R9") (pin "2") (pinfunction "2_2") (pintype "passive"))
      (node (ref "U$25") (pin "14") (pinfunction "P2.4/PWM_14") (pintype "bidirectional"))
      (node (ref "U$26") (pin "14") (pinfunction "P2.4/PWM_14") (pintype "bidirectional"))
    )
    (net (code "35") (name "/MTR_MOTOR_FLT#") (class "Default")
      (node (ref "IC22") (pin "4") (pinfunction "FLT#_4") (pintype "bidirectional"))
      (node (ref "R15") (pin "2") (pinfunction "2_2") (pintype "passive"))
      (node (ref "U$25") (pin "17") (pinfunction "P1.29_17") (pintype "bidirectional"))
      (node (ref "U$26") (pin "17") (pinfunction "P1.29_17") (pintype "bidirectional"))
    )
    (net (code "36") (name "/MTR_MOTOR_PWM") (class "Default")
      (node (ref "IC22") (pin "6") (pinfunction "PWM_6") (pintype "bidirectional"))
      (node (ref "JP21") (pin "2") (pinfunction "2_2") (pintype "passive"))
      (node (ref "R1") (pin "2") (pinfunction "2_2") (pintype "passive"))
      (node (ref "R11") (pin "1") (pinfunction "1_1") (pintype "passive"))
      (node (ref "U$25") (pin "8") (pinfunction "P2.1/PWM_8") (pintype "bidirectional"))
      (node (ref "U$26") (pin "8") (pinfunction "P2.1/PWM_8") (pintype "bidirectional"))
    )
    (net (code "37") (name "/MTR_SCK") (class "Default")
      (node (ref "U$12") (pin "8") (pinfunction "SCK_8") (pintype "bidirectional"))
      (node (ref "U$25") (pin "5") (pinfunction "P0.7/SCK1_5") (pintype "bidirectional"))
      (node (ref "U$26") (pin "5") (pinfunction "P0.7/SCK1_5") (pintype "bidirectional"))
    )
    (net (code "38") (name "/MTR_SD_CS#") (class "Default")
      (node (ref "U$12") (pin "5") (pinfunction "CARD_CS#_5") (pintype "bidirectional"))
      (node (ref "U$25") (pin "27") (pinfunction "P1.19_27") (pintype "bidirectional"))
      (node (ref "U$26") (pin "27") (pinfunction "P1.19_27") (pintype "bidirectional"))
    )
    (net (code "39") (name "/MTR_STEER_EN#") (class "Default")
      (node (ref "JP21") (pin "3") (pinfunction "3_3") (pintype "passive"))
      (node (ref "R10") (pin "2") (pinfunction "2_2") (pintype "passive"))
      (node (ref "U$25") (pin "12") (pinfunction "P2.3/PWM_12") (pintype "bidirectional"))
      (node (ref "U$26") (pin "12") (pinfunction "P2.3/PWM_12") (pintype "bidirectional"))
    )
    (net (code "40") (name "/MTR_STEER_PWM") (class "Default")
      (node (ref "JP19") (pin "1") (pinfunction "1_1") (pintype "passive"))
      (node (ref "JP21") (pin "4") (pinfunction "4_4") (pintype "passive"))
      (node (ref "R12") (pin "1") (pinfunction "1_1") (pintype "passive"))
      (node (ref "R21") (pin "2") (pinfunction "2_2") (pintype "passive"))
      (node (ref "U$25") (pin "6") (pinfunction "P2.0/PWM_6") (pintype "bidirectional"))
      (node (ref "U$26") (pin "6") (pinfunction "P2.0/PWM_6") (pintype "bidirectional"))
    )
    (net (code "41") (name "/MTR_TACH#") (class "Default")
      (node (ref "JP20") (pin "3") (pinfunction "3_3") (pintype "passive"))
      (node (ref "R13") (pin "1") (pinfunction "1_1") (pintype "passive"))
      (node (ref "U$25") (pin "18") (pinfunction "P2.6/PWM_18") (pintype "bidirectional"))
      (node (ref "U$26") (pin "18") (pinfunction "P2.6/PWM_18") (pintype "bidirectional"))
    )
    (net (code "42") (name "/MTR_TFT_CS#") (class "Default")
      (node (ref "U$12") (pin "6") (pinfunction "TFT_CS#_6") (pintype "bidirectional"))
      (node (ref "U$25") (pin "25") (pinfunction "P1.20_25") (pintype "bidirectional"))
      (node (ref "U$26") (pin "25") (pinfunction "P1.20_25") (pintype "bidirectional"))
    )
    (net (code "43") (name "/MTR_TFT_D{slash}C#") (class "Default")
      (node (ref "U$12") (pin "4") (pinfunction "D/C#_4") (pintype "bidirectional"))
      (node (ref "U$25") (pin "23") (pinfunction "P1.22_23") (pintype "bidirectional"))
      (node (ref "U$26") (pin "23") (pinfunction "P1.22_23") (pintype "bidirectional"))
    )
    (net (code "44") (name "/MTR_TFT_RESET#") (class "Default")
      (node (ref "U$12") (pin "3") (pinfunction "RESET#_3") (pintype "bidirectional"))
      (node (ref "U$25") (pin "21") (pinfunction "P1.23_21") (pintype "bidirectional"))
      (node (ref "U$26") (pin "21") (pinfunction "P1.23_21") (pintype "bidirectional"))
    )
    (net (code "45") (name "/N$211") (class "Default")
      (node (ref "U$19") (pin "18") (pinfunction "P2.6/PWM_18") (pintype "bidirectional"))
      (node (ref "U$20") (pin "18") (pinfunction "P2.6/PWM_18") (pintype "bidirectional"))
    )
    (net (code "46") (name "/N$216") (class "Default")
      (node (ref "U$19") (pin "20") (pinfunction "P2.7/PWM/CAN2RX_20") (pintype "bidirectional"))
      (node (ref "U$20") (pin "20") (pinfunction "P2.7/PWM/CAN2RX_20") (pintype "bidirectional"))
    )
    (net (code "47") (name "/N$217") (class "Default")
      (node (ref "U$19") (pin "22") (pinfunction "P2.8/CAN2TX/TXD2_22") (pintype "bidirectional"))
      (node (ref "U$20") (pin "22") (pinfunction "P2.8/CAN2TX/TXD2_22") (pintype "bidirectional"))
    )
    (net (code "48") (name "/N$218") (class "Default")
      (node (ref "U$19") (pin "24") (pinfunction "P2.9/RXD2_24") (pintype "bidirectional"))
      (node (ref "U$20") (pin "24") (pinfunction "P2.9/RXD2_24") (pintype "bidirectional"))
    )
    (net (code "49") (name "/N$219") (class "Default")
      (node (ref "U$19") (pin "26") (pinfunction "P0.15/SCK0_26") (pintype "bidirectional"))
      (node (ref "U$20") (pin "26") (pinfunction "P0.15/SCK0_26") (pintype "bidirectional"))
    )
    (net (code "50") (name "/N$220") (class "Default")
      (node (ref "U$19") (pin "28") (pinfunction "P0.17/MISO0_28") (pintype "bidirectional"))
      (node (ref "U$20") (pin "28") (pinfunction "P0.17/MISO0_28") (pintype "bidirectional"))
    )
    (net (code "51") (name "/N$221") (class "Default")
      (node (ref "U$19") (pin "30") (pinfunction "P0.18/MOSI0_30") (pintype "bidirectional"))
      (node (ref "U$20") (pin "30") (pinfunction "P0.18/MOSI0_30") (pintype "bidirectional"))
    )
    (net (code "52") (name "/N$224") (class "Default")
      (node (ref "U$19") (pin "1") (pinfunction "P4.29/RXD3_1") (pintype "bidirectional"))
      (node (ref "U$20") (pin "1") (pinfunction "P4.29/RXD3_1") (pintype "bidirectional"))
    )
    (net (code "53") (name "/N$225") (class "Default")
      (node (ref "U$19") (pin "3") (pinfunction "P4.28/TXD3_3") (pintype "bidirectional"))
      (node (ref "U$20") (pin "3") (pinfunction "P4.28/TXD3_3") (pintype "bidirectional"))
    )
    (net (code "54") (name "/N$226") (class "Default")
      (node (ref "U$19") (pin "5") (pinfunction "P0.7/SCK1_5") (pintype "bidirectional"))
      (node (ref "U$20") (pin "5") (pinfunction "P0.7/SCK1_5") (pintype "bidirectional"))
    )
    (net (code "55") (name "/N$227") (class "Default")
      (node (ref "U$19") (pin "7") (pinfunction "P0.8/MISO1_7") (pintype "bidirectional"))
      (node (ref "U$20") (pin "7") (pinfunction "P0.8/MISO1_7") (pintype "bidirectional"))
    )
    (net (code "56") (name "/N$228") (class "Default")
      (node (ref "U$19") (pin "9") (pinfunction "P0.9/MOSI1_9") (pintype "bidirectional"))
      (node (ref "U$20") (pin "9") (pinfunction "P0.9/MOSI1_9") (pintype "bidirectional"))
    )
    (net (code "57") (name "/N$230") (class "Default")
      (node (ref "U$19") (pin "13") (pinfunction "P1.31/ADC_13") (pintype "bidirectional"))
      (node (ref "U$20") (pin "13") (pinfunction "P1.31/ADC_13") (pintype "bidirectional"))
    )
    (net (code "58") (name "/N$231") (class "Default")
      (node (ref "U$19") (pin "15") (pinfunction "P1.30/ADC_15") (pintype "bidirectional"))
      (node (ref "U$20") (pin "15") (pinfunction "P1.30/ADC_15") (pintype "bidirectional"))
    )
    (net (code "59") (name "/N$232") (class "Default")
      (node (ref "U$19") (pin "17") (pinfunction "P1.29_17") (pintype "bidirectional"))
      (node (ref "U$20") (pin "17") (pinfunction "P1.29_17") (pintype "bidirectional"))
    )
    (net (code "60") (name "/N$233") (class "Default")
      (node (ref "U$19") (pin "19") (pinfunction "P1.28_19") (pintype "bidirectional"))
      (node (ref "U$20") (pin "19") (pinfunction "P1.28_19") (pintype "bidirectional"))
    )
    (net (code "61") (name "/N$234") (class "Default")
      (node (ref "U$19") (pin "21") (pinfunction "P1.23_21") (pintype "bidirectional"))
      (node (ref "U$20") (pin "21") (pinfunction "P1.23_21") (pintype "bidirectional"))
    )
    (net (code "62") (name "/N$235") (class "Default")
      (node (ref "U$19") (pin "23") (pinfunction "P1.22_23") (pintype "bidirectional"))
      (node (ref "U$20") (pin "23") (pinfunction "P1.22_23") (pintype "bidirectional"))
    )
    (net (code "63") (name "/N$236") (class "Default")
      (node (ref "U$19") (pin "25") (pinfunction "P1.20_25") (pintype "bidirectional"))
      (node (ref "U$20") (pin "25") (pinfunction "P1.20_25") (pintype "bidirectional"))
    )
    (net (code "64") (name "/OUT3") (class "Default")
      (node (ref "IC1") (pin "3") (pinfunction "1C3_3") (pintype "input"))
      (node (ref "IC4") (pin "7") (pinfunction "Q3_7") (pintype "output"))
      (node (ref "JP23") (pin "1") (pinfunction "1_1") (pintype "passive"))
    )
    (net (code "65") (name "/OUT7") (class "Default")
      (node (ref "IC1") (pin "13") (pinfunction "2C3_13") (pintype "input"))
      (node (ref "IC4") (pin "12") (pinfunction "Q7_12") (pintype "output"))
      (node (ref "JP23") (pin "2") (pinfunction "2_2") (pintype "passive"))
    )
    (net (code "66") (name "/OUTA") (class "Default")
      (node (ref "IC22") (pin "15") (pinfunction "OUTA_15") (pintype "bidirectional"))
      (node (ref "IC22") (pin "16") (pinfunction "OUTA_16") (pintype "bidirectional"))
    )
    (net (code "67") (name "/OUTB") (class "Default")
      (node (ref "IC22") (pin "13") (pinfunction "OUTB_13") (pintype "bidirectional"))
      (node (ref "IC22") (pin "14") (pinfunction "OUTB_14") (pintype "bidirectional"))
    )
    (net (code "68") (name "/SFC_AN") (class "Default")
      (node (ref "JP14") (pin "5") (pinfunction "5_5") (pintype "passive"))
    )
    (net (code "69") (name "/SFC_BW") (class "Default")
      (node (ref "JP14") (pin "7") (pinfunction "7_7") (pintype "passive"))
    )
    (net (code "70") (name "/SFC_ECHO") (class "Default")
      (node (ref "IC1") (pin "5") (pinfunction "1C1_5") (pintype "input"))
      (node (ref "JP12") (pin "5") (pinfunction "5_5") (pintype "passive"))
      (node (ref "JP14") (pin "6") (pinfunction "6_6") (pintype "passive"))
    )
    (net (code "71") (name "/SFC_TRG") (class "Default")
      (node (ref "IC4") (pin "5") (pinfunction "Q1_5") (pintype "output"))
      (node (ref "JP12") (pin "6") (pinfunction "6_6") (pintype "passive"))
      (node (ref "JP14") (pin "4") (pinfunction "4_4") (pintype "passive"))
      (node (ref "JP8") (pin "3") (pinfunction "3_3") (pintype "passive"))
    )
    (net (code "72") (name "/SFC_TXD") (class "Default")
      (node (ref "JP14") (pin "3") (pinfunction "3_3") (pintype "passive"))
    )
    (net (code "73") (name "/SFL_AN") (class "Default")
      (node (ref "JP13") (pin "5") (pinfunction "5_5") (pintype "passive"))
    )
    (net (code "74") (name "/SFL_BW") (class "Default")
      (node (ref "JP13") (pin "7") (pinfunction "7_7") (pintype "passive"))
    )
    (net (code "75") (name "/SFL_ECHO") (class "Default")
      (node (ref "IC1") (pin "6") (pinfunction "1C0_6") (pintype "input"))
      (node (ref "JP12") (pin "3") (pinfunction "3_3") (pintype "passive"))
      (node (ref "JP13") (pin "6") (pinfunction "6_6") (pintype "passive"))
    )
    (net (code "76") (name "/SFL_TRG") (class "Default")
      (node (ref "IC4") (pin "4") (pinfunction "Q0_4") (pintype "output"))
      (node (ref "JP12") (pin "4") (pinfunction "4_4") (pintype "passive"))
      (node (ref "JP13") (pin "4") (pinfunction "4_4") (pintype "passive"))
      (node (ref "JP2") (pin "3") (pinfunction "3_3") (pintype "passive"))
    )
    (net (code "77") (name "/SFL_TXD") (class "Default")
      (node (ref "JP13") (pin "3") (pinfunction "3_3") (pintype "passive"))
    )
    (net (code "78") (name "/SFR_AN") (class "Default")
      (node (ref "JP15") (pin "5") (pinfunction "5_5") (pintype "passive"))
    )
    (net (code "79") (name "/SFR_BW") (class "Default")
      (node (ref "JP15") (pin "7") (pinfunction "7_7") (pintype "passive"))
    )
    (net (code "80") (name "/SFR_ECHO") (class "Default")
      (node (ref "IC1") (pin "4") (pinfunction "1C2_4") (pintype "input"))
      (node (ref "JP12") (pin "7") (pinfunction "7_7") (pintype "passive"))
      (node (ref "JP15") (pin "6") (pinfunction "6_6") (pintype "passive"))
    )
    (net (code "81") (name "/SFR_TRG") (class "Default")
      (node (ref "IC4") (pin "6") (pinfunction "Q2_6") (pintype "output"))
      (node (ref "JP12") (pin "8") (pinfunction "8_8") (pintype "passive"))
      (node (ref "JP15") (pin "4") (pinfunction "4_4") (pintype "passive"))
      (node (ref "JP9") (pin "3") (pinfunction "3_3") (pintype "passive"))
    )
    (net (code "82") (name "/SFR_TXD") (class "Default")
      (node (ref "JP15") (pin "3") (pinfunction "3_3") (pintype "passive"))
    )
    (net (code "83") (name "/SNS_3V3") (class "Default")
      (node (ref "C5") (pin "1") (pinfunction "1_1") (pintype "passive"))
      (node (ref "IC2") (pin "3") (pinfunction "3V3_3") (pintype "bidirectional"))
      (node (ref "IMU_MDL") (pin "P3") (pinfunction "VDD_P3") (pintype "bidirectional"))
      (node (ref "JP11") (pin "3") (pinfunction "3_3") (pintype "passive"))
      (node (ref "U$19") (pin "2") (pinfunction "3V3_2") (pintype "bidirectional"))
      (node (ref "U$20") (pin "2") (pinfunction "3V3_2") (pintype "bidirectional"))
      (node (ref "U$9") (pin "1") (pinfunction "VCC_1") (pintype "bidirectional"))
    )
    (net (code "84") (name "/SNS_CAN_RX") (class "Default")
      (node (ref "IC2") (pin "4") (pinfunction "CAN_OUT(R)_4") (pintype "bidirectional"))
      (node (ref "U$19") (pin "34") (pinfunction "P0.0/CAN1RX_34") (pintype "bidirectional"))
      (node (ref "U$20") (pin "34") (pinfunction "P0.0/CAN1RX_34") (pintype "bidirectional"))
      (node (ref "U$9") (pin "3") (pinfunction "CAN-RX_3") (pintype "bidirectional"))
    )
    (net (code "85") (name "/SNS_CAN_TX") (class "Default")
      (node (ref "IC2") (pin "1") (pinfunction "CAN_IN(D)_1") (pintype "bidirectional"))
      (node (ref "U$19") (pin "32") (pinfunction "P0.1/CAN1TX_32") (pintype "bidirectional"))
      (node (ref "U$20") (pin "32") (pinfunction "P0.1/CAN1TX_32") (pintype "bidirectional"))
      (node (ref "U$9") (pin "4") (pinfunction "CAN-TX_4") (pintype "bidirectional"))
    )
    (net (code "86") (name "/SNS_DIN") (class "Default")
      (node (ref "IC4") (pin "13") (pinfunction "D_13") (pintype "input"))
      (node (ref "U$19") (pin "12") (pinfunction "P2.3/PWM_12") (pintype "bidirectional"))
      (node (ref "U$20") (pin "12") (pinfunction "P2.3/PWM_12") (pintype "bidirectional"))
    )
    (net (code "87") (name "/SNS_DOUT") (class "Default")
      (node (ref "U$19") (pin "16") (pinfunction "P2.5/PWM_16") (pintype "bidirectional"))
      (node (ref "U$20") (pin "16") (pinfunction "P2.5/PWM_16") (pintype "bidirectional"))
    )
    (net (code "88") (name "/SNS_ECHO_CAP") (class "Default")
      (node (ref "IC1") (pin "7") (pinfunction "1Y_7") (pintype "tri_state"))
      (node (ref "U$19") (pin "27") (pinfunction "P1.19_27") (pintype "bidirectional"))
      (node (ref "U$20") (pin "27") (pinfunction "P1.19_27") (pintype "bidirectional"))
    )
    (net (code "89") (name "/SNS_LE") (class "Default")
      (node (ref "IC4") (pin "14") (pinfunction "G_14") (pintype "input"))
      (node (ref "U$19") (pin "14") (pinfunction "P2.4/PWM_14") (pintype "bidirectional"))
      (node (ref "U$20") (pin "14") (pinfunction "P2.4/PWM_14") (pintype "bidirectional"))
    )
    (net (code "90") (name "/SNS_SCL") (class "Default")
      (node (ref "IMU_MDL") (pin "P1") (pinfunction "SCL_P1") (pintype "bidirectional"))
      (node (ref "JP1") (pin "2") (pinfunction "2_2") (pintype "passive"))
      (node (ref "JP11") (pin "1") (pinfunction "1_1") (pintype "passive"))
    )
    (net (code "91") (name "/SNS_SDA") (class "Default")
      (node (ref "IMU_MDL") (pin "P2") (pinfunction "SDA_P2") (pintype "bidirectional"))
      (node (ref "JP1") (pin "1") (pinfunction "1_1") (pintype "passive"))
      (node (ref "JP11") (pin "2") (pinfunction "2_2") (pintype "passive"))
    )
    (net (code "92") (name "/SNS_SEL0") (class "Default")
      (node (ref "IC1") (pin "14") (pinfunction "A_14") (pintype "input"))
      (node (ref "IC4") (pin "1") (pinfunction "S0_1") (pintype "input"))
      (node (ref "U$19") (pin "6") (pinfunction "P2.0/PWM_6") (pintype "bidirectional"))
      (node (ref "U$20") (pin "6") (pinfunction "P2.0/PWM_6") (pintype "bidirectional"))
    )
    (net (code "93") (name "/SNS_SEL1") (class "Default")
      (node (ref "IC1") (pin "2") (pinfunction "B_2") (pintype "input"))
      (node (ref "IC4") (pin "2") (pinfunction "S1_2") (pintype "input"))
      (node (ref "U$19") (pin "8") (pinfunction "P2.1/PWM_8") (pintype "bidirectional"))
      (node (ref "U$20") (pin "8") (pinfunction "P2.1/PWM_8") (pintype "bidirectional"))
    )
    (net (code "94") (name "/SNS_SEL2") (class "Default")
      (node (ref "IC4") (pin "3") (pinfunction "S2_3") (pintype "input"))
      (node (ref "U$19") (pin "10") (pinfunction "P2.2/PWM_10") (pintype "bidirectional"))
      (node (ref "U$20") (pin "10") (pinfunction "P2.2/PWM_10") (pintype "bidirectional"))
    )
    (net (code "95") (name "/SRC_AN") (class "Default")
      (node (ref "JP17") (pin "5") (pinfunction "5_5") (pintype "passive"))
    )
    (net (code "96") (name "/SRC_BW") (class "Default")
      (node (ref "JP17") (pin "7") (pinfunction "7_7") (pintype "passive"))
    )
    (net (code "97") (name "/SRC_ECHO") (class "Default")
      (node (ref "IC1") (pin "11") (pinfunction "2C1_11") (pintype "input"))
      (node (ref "JP12") (pin "11") (pinfunction "11_11") (pintype "passive"))
      (node (ref "JP17") (pin "6") (pinfunction "6_6") (pintype "passive"))
    )
    (net (code "98") (name "/SRC_TRG") (class "Default")
      (node (ref "JP12") (pin "12") (pinfunction "12_12") (pintype "passive"))
      (node (ref "JP17") (pin "4") (pinfunction "4_4") (pintype "passive"))
      (node (ref "JP8") (pin "2") (pinfunction "2_2") (pintype "passive"))
    )
    (net (code "99") (name "/SRC_TXD") (class "Default")
      (node (ref "JP17") (pin "3") (pinfunction "3_3") (pintype "passive"))
    )
    (net (code "100") (name "/SRL_AN") (class "Default")
      (node (ref "JP16") (pin "5") (pinfunction "5_5") (pintype "passive"))
    )
    (net (code "101") (name "/SRL_BW") (class "Default")
      (node (ref "JP16") (pin "7") (pinfunction "7_7") (pintype "passive"))
    )
    (net (code "102") (name "/SRL_ECHO") (class "Default")
      (node (ref "IC1") (pin "10") (pinfunction "2C0_10") (pintype "input"))
      (node (ref "JP12") (pin "9") (pinfunction "9_9") (pintype "passive"))
      (node (ref "JP16") (pin "6") (pinfunction "6_6") (pintype "passive"))
    )
    (net (code "103") (name "/SRL_TRG") (class "Default")
      (node (ref "JP12") (pin "10") (pinfunction "10_10") (pintype "passive"))
      (node (ref "JP16") (pin "4") (pinfunction "4_4") (pintype "passive"))
      (node (ref "JP2") (pin "2") (pinfunction "2_2") (pintype "passive"))
    )
    (net (code "104") (name "/SRL_TXD") (class "Default")
      (node (ref "JP16") (pin "3") (pinfunction "3_3") (pintype "passive"))
    )
    (net (code "105") (name "/SRR_AN") (class "Default")
      (node (ref "JP18") (pin "5") (pinfunction "5_5") (pintype "passive"))
    )
    (net (code "106") (name "/SRR_BW") (class "Default")
      (node (ref "JP18") (pin "7") (pinfunction "7_7") (pintype "passive"))
    )
    (net (code "107") (name "/SRR_ECHO") (class "Default")
      (node (ref "IC1") (pin "12") (pinfunction "2C2_12") (pintype "input"))
      (node (ref "JP12") (pin "13") (pinfunction "13_13") (pintype "passive"))
      (node (ref "JP18") (pin "6") (pinfunction "6_6") (pintype "passive"))
    )
    (net (code "108") (name "/SRR_TRG") (class "Default")
      (node (ref "JP12") (pin "14") (pinfunction "14_14") (pintype "passive"))
      (node (ref "JP18") (pin "4") (pinfunction "4_4") (pintype "passive"))
      (node (ref "JP9") (pin "2") (pinfunction "2_2") (pintype "passive"))
    )
    (net (code "109") (name "/SRR_TXD") (class "Default")
      (node (ref "JP18") (pin "3") (pinfunction "3_3") (pintype "passive"))
    )
    (net (code "110") (name "/SYSRST#") (class "Default")
      (node (ref "IC23") (pin "1") (pinfunction "RST#_1") (pintype "open_collector"))
      (node (ref "IC4") (pin "15") (pinfunction "CLR_15") (pintype "input"))
    )
    (net (code "111") (name "/USFEN#") (class "Default")
      (node (ref "IC21") (pin "3") (pinfunction "EN1#_3") (pintype "bidirectional"))
      (node (ref "R26") (pin "2") (pinfunction "2_2") (pintype "passive"))
      (node (ref "U$19") (pin "29") (pinfunction "P0.30_29") (pintype "bidirectional"))
      (node (ref "U$20") (pin "29") (pinfunction "P0.30_29") (pintype "bidirectional"))
    )
    (net (code "112") (name "/USFOC#") (class "Default")
      (node (ref "IC21") (pin "8") (pinfunction "FLT1#_8") (pintype "bidirectional"))
      (node (ref "LED1") (pin "C") (pinfunction "C_C") (pintype "passive"))
      (node (ref "R24") (pin "2") (pinfunction "2_2") (pintype "passive"))
    )
    (net (code "113") (name "/USFVCC") (class "Default")
      (node (ref "C13") (pin "1") (pinfunction "1_1") (pintype "passive"))
      (node (ref "C14") (pin "1") (pinfunction "1_1") (pintype "passive"))
      (node (ref "C15") (pin "1") (pinfunction "1_1") (pintype "passive"))
      (node (ref "C16") (pin "1") (pinfunction "1_1") (pintype "passive"))
      (node (ref "C19") (pin "+") (pinfunction "+_+") (pintype "passive"))
      (node (ref "IC21") (pin "7") (pinfunction "OUT1_7") (pintype "bidirectional"))
      (node (ref "JP13") (pin "2") (pinfunction "2_2") (pintype "passive"))
      (node (ref "JP14") (pin "2") (pinfunction "2_2") (pintype "passive"))
      (node (ref "JP15") (pin "2") (pinfunction "2_2") (pintype "passive"))
      (node (ref "R29") (pin "2") (pinfunction "2_2") (pintype "passive"))
    )
    (net (code "114") (name "/USREN#") (class "Default")
      (node (ref "IC21") (pin "4") (pinfunction "EN2#_4") (pintype "bidirectional"))
      (node (ref "R27") (pin "2") (pinfunction "2_2") (pintype "passive"))
      (node (ref "U$19") (pin "31") (pinfunction "P0.29_31") (pintype "bidirectional"))
      (node (ref "U$20") (pin "31") (pinfunction "P0.29_31") (pintype "bidirectional"))
    )
    (net (code "115") (name "/USROC#") (class "Default")
      (node (ref "IC21") (pin "5") (pinfunction "FLT2#_5") (pintype "bidirectional"))
      (node (ref "LED3") (pin "C") (pinfunction "C_C") (pintype "passive"))
      (node (ref "R25") (pin "2") (pinfunction "2_2") (pintype "passive"))
    )
    (net (code "116") (name "/USRVCC") (class "Default")
      (node (ref "C10") (pin "1") (pinfunction "1_1") (pintype "passive"))
      (node (ref "C11") (pin "1") (pinfunction "1_1") (pintype "passive"))
      (node (ref "C12") (pin "1") (pinfunction "1_1") (pintype "passive"))
      (node (ref "C17") (pin "1") (pinfunction "1_1") (pintype "passive"))
      (node (ref "C18") (pin "+") (pinfunction "+_+") (pintype "passive"))
      (node (ref "IC21") (pin "6") (pinfunction "OUT2_6") (pintype "bidirectional"))
      (node (ref "JP16") (pin "2") (pinfunction "2_2") (pintype "passive"))
      (node (ref "JP17") (pin "2") (pinfunction "2_2") (pintype "passive"))
      (node (ref "JP18") (pin "2") (pinfunction "2_2") (pintype "passive"))
      (node (ref "R30") (pin "2") (pinfunction "2_2") (pintype "passive"))
    )
    (net (code "117") (name "GND") (class "Default")
      (node (ref "C1") (pin "2") (pinfunction "2_2") (pintype "passive"))
      (node (ref "C10") (pin "2") (pinfunction "2_2") (pintype "passive"))
      (node (ref "C11") (pin "2") (pinfunction "2_2") (pintype "passive"))
      (node (ref "C12") (pin "2") (pinfunction "2_2") (pintype "passive"))
      (node (ref "C13") (pin "2") (pinfunction "2_2") (pintype "passive"))
      (node (ref "C14") (pin "2") (pinfunction "2_2") (pintype "passive"))
      (node (ref "C15") (pin "2") (pinfunction "2_2") (pintype "passive"))
      (node (ref "C16") (pin "2") (pinfunction "2_2") (pintype "passive"))
      (node (ref "C17") (pin "2") (pinfunction "2_2") (pintype "passive"))
      (node (ref "C18") (pin "-") (pinfunction "-_-") (pintype "passive"))
      (node (ref "C19") (pin "-") (pinfunction "-_-") (pintype "passive"))
      (node (ref "C2") (pin "2") (pinfunction "2_2") (pintype "passive"))
      (node (ref "C20") (pin "2") (pinfunction "2_2") (pintype "passive"))
      (node (ref "C21") (pin "2") (pinfunction "2_2") (pintype "passive"))
      (node (ref "C23") (pin "-") (pinfunction "-_-") (pintype "passive"))
      (node (ref "C24") (pin "-") (pinfunction "-_-") (pintype "passive"))
      (node (ref "C25") (pin "-") (pinfunction "-_-") (pintype "passive"))
      (node (ref "C3") (pin "2") (pinfunction "2_2") (pintype "passive"))
      (node (ref "C4") (pin "2") (pinfunction "2_2") (pintype "passive"))
      (node (ref "C5") (pin "2") (pinfunction "2_2") (pintype "passive"))
      (node (ref "C6") (pin "2") (pinfunction "2_2") (pintype "passive"))
      (node (ref "C7") (pin "2") (pinfunction "2_2") (pintype "passive"))
      (node (ref "C8") (pin "2") (pinfunction "2_2") (pintype "passive"))
      (node (ref "C9") (pin "2") (pinfunction "2_2") (pintype "passive"))
      (node (ref "D1") (pin "A") (pinfunction "A_A") (pintype "passive"))
      (node (ref "IC1") (pin "1") (pinfunction "1G_1") (pintype "input"))
      (node (ref "IC1") (pin "15") (pinfunction "2G_15") (pintype "input"))
      (node (ref "IC1") (pin "8") (pinfunction "GND_8") (pintype "power_in"))
      (node (ref "IC10") (pin "2") (pinfunction "GND_2") (pintype "bidirectional"))
      (node (ref "IC2") (pin "2") (pinfunction "GND_2") (pintype "bidirectional"))
      (node (ref "IC20") (pin "2") (pinfunction "SOURCE_2") (pintype "bidirectional"))
      (node (ref "IC21") (pin "1") (pinfunction "GND_1") (pintype "bidirectional"))
      (node (ref "IC22") (pin "11") (pinfunction "GND_11") (pintype "bidirectional"))
      (node (ref "IC22") (pin "12") (pinfunction "GND_12") (pintype "bidirectional"))
      (node (ref "IC22") (pin "8") (pinfunction "GND_8") (pintype "bidirectional"))
      (node (ref "IC22") (pin "9") (pinfunction "GND_9") (pintype "bidirectional"))
      (node (ref "IC23") (pin "3") (pinfunction "GND_3") (pintype "power_in"))
      (node (ref "IC4") (pin "8") (pinfunction "GND_8") (pintype "power_in"))
      (node (ref "IC6") (pin "2") (pinfunction "GND_2") (pintype "bidirectional"))
      (node (ref "IC7") (pin "2") (pinfunction "GND_2") (pintype "bidirectional"))
      (node (ref "IC8") (pin "2") (pinfunction "GND_2") (pintype "bidirectional"))
      (node (ref "IMU_MDL") (pin "P4") (pinfunction "GND_P4") (pintype "bidirectional"))
      (node (ref "JP1") (pin "5") (pinfunction "5_5") (pintype "passive"))
      (node (ref "JP10") (pin "3") (pinfunction "3_3") (pintype "passive"))
      (node (ref "JP11") (pin "4") (pinfunction "4_4") (pintype "passive"))
      (node (ref "JP12") (pin "1") (pinfunction "1_1") (pintype "passive"))
      (node (ref "JP12") (pin "2") (pinfunction "2_2") (pintype "passive"))
      (node (ref "JP13") (pin "1") (pinfunction "1_1") (pintype "passive"))
      (node (ref "JP14") (pin "1") (pinfunction "1_1") (pintype "passive"))
      (node (ref "JP15") (pin "1") (pinfunction "1_1") (pintype "passive"))
      (node (ref "JP16") (pin "1") (pinfunction "1_1") (pintype "passive"))
      (node (ref "JP17") (pin "1") (pinfunction "1_1") (pintype "passive"))
      (node (ref "JP18") (pin "1") (pinfunction "1_1") (pintype "passive"))
      (node (ref "JP19") (pin "2") (pinfunction "2_2") (pintype "passive"))
      (node (ref "JP20") (pin "2") (pinfunction "2_2") (pintype "passive"))
      (node (ref "JP21") (pin "5") (pinfunction "5_5") (pintype "passive"))
      (node (ref "JP21") (pin "7") (pinfunction "7_7") (pintype "passive"))
      (node (ref "JP22") (pin "2") (pinfunction "2_2") (pintype "passive"))
      (node (ref "JP22") (pin "4") (pinfunction "4_4") (pintype "passive"))
      (node (ref "JP22") (pin "6") (pinfunction "6_6") (pintype "passive"))
      (node (ref "JP23") (pin "3") (pinfunction "3_3") (pintype "passive"))
      (node (ref "JP30") (pin "2") (pinfunction "2_2") (pintype "passive"))
      (node (ref "JP31") (pin "2") (pinfunction "2_2") (pintype "passive"))
      (node (ref "JP32") (pin "2") (pinfunction "2_2") (pintype "passive"))
      (node (ref "JP33") (pin "2") (pinfunction "2_2") (pintype "passive"))
      (node (ref "JP34") (pin "2") (pinfunction "2_2") (pintype "passive"))
      (node (ref "JP37") (pin "2") (pinfunction "2_2") (pintype "passive"))
      (node (ref "LED2") (pin "C") (pinfunction "C_C") (pintype "passive"))
      (node (ref "LED4") (pin "C") (pinfunction "C_C") (pintype "passive"))
      (node (ref "LED5") (pin "C") (pinfunction "C_C") (pintype "passive"))
      (node (ref "R1") (pin "1") (pinfunction "1_1") (pintype "passive"))
      (node (ref "R11") (pin "2") (pinfunction "2_2") (pintype "passive"))
      (node (ref "R12") (pin "2") (pinfunction "2_2") (pintype "passive"))
      (node (ref "R19") (pin "2") (pinfunction "2_2") (pintype "passive"))
      (node (ref "R20") (pin "2") (pinfunction "2_2") (pintype "passive"))
      (node (ref "R21") (pin "1") (pinfunction "1_1") (pintype "passive"))
      (node (ref "R22") (pin "2") (pinfunction "2_2") (pintype "passive"))
      (node (ref "R4") (pin "2") (pinfunction "2_2") (pintype "passive"))
      (node (ref "R5") (pin "2") (pinfunction "2_2") (pintype "passive"))
      (node (ref "R6") (pin "2") (pinfunction "2_2") (pintype "passive"))
      (node (ref "R7") (pin "2") (pinfunction "2_2") (pintype "passive"))
      (node (ref "R8") (pin "2") (pinfunction "2_2") (pintype "passive"))
      (node (ref "S1") (pin "3") (pinfunction "P_3") (pintype "passive"))
      (node (ref "S1") (pin "4") (pinfunction "P1_4") (pintype "passive"))
      (node (ref "S2") (pin "3") (pinfunction "P_3") (pintype "passive"))
      (node (ref "S2") (pin "4") (pinfunction "P1_4") (pintype "passive"))
      (node (ref "U$10") (pin "2") (pinfunction "GND_2") (pintype "bidirectional"))
      (node (ref "U$11") (pin "2") (pinfunction "GND_2") (pintype "bidirectional"))
      (node (ref "U$12") (pin "1") (pinfunction "GND_1") (pintype "bidirectional"))
      (node (ref "U$13") (pin "P7") (pinfunction "GND_P7") (pintype "bidirectional"))
      (node (ref "U$19") (pin "33") (pinfunction "GND_33") (pintype "bidirectional"))
      (node (ref "U$19") (pin "4") (pinfunction "GND_4") (pintype "bidirectional"))
      (node (ref "U$20") (pin "33") (pinfunction "GND_33") (pintype "bidirectional"))
      (node (ref "U$20") (pin "4") (pinfunction "GND_4") (pintype "bidirectional"))
      (node (ref "U$23") (pin "33") (pinfunction "GND_33") (pintype "bidirectional"))
      (node (ref "U$23") (pin "4") (pinfunction "GND_4") (pintype "bidirectional"))
      (node (ref "U$24") (pin "33") (pinfunction "GND_33") (pintype "bidirectional"))
      (node (ref "U$24") (pin "4") (pinfunction "GND_4") (pintype "bidirectional"))
      (node (ref "U$25") (pin "33") (pinfunction "GND_33") (pintype "bidirectional"))
      (node (ref "U$25") (pin "4") (pinfunction "GND_4") (pintype "bidirectional"))
      (node (ref "U$26") (pin "33") (pinfunction "GND_33") (pintype "bidirectional"))
      (node (ref "U$26") (pin "4") (pinfunction "GND_4") (pintype "bidirectional"))
      (node (ref "U$27") (pin "33") (pinfunction "GND_33") (pintype "bidirectional"))
      (node (ref "U$27") (pin "4") (pinfunction "GND_4") (pintype "bidirectional"))
      (node (ref "U$28") (pin "33") (pinfunction "GND_33") (pintype "bidirectional"))
      (node (ref "U$28") (pin "4") (pinfunction "GND_4") (pintype "bidirectional"))
      (node (ref "U$29") (pin "33") (pinfunction "GND_33") (pintype "bidirectional"))
      (node (ref "U$29") (pin "4") (pinfunction "GND_4") (pintype "bidirectional"))
      (node (ref "U$30") (pin "33") (pinfunction "GND_33") (pintype "bidirectional"))
      (node (ref "U$30") (pin "4") (pinfunction "GND_4") (pintype "bidirectional"))
      (node (ref "U$7") (pin "2") (pinfunction "GND_2") (pintype "bidirectional"))
      (node (ref "U$8") (pin "2") (pinfunction "GND_2") (pintype "bidirectional"))
      (node (ref "U$9") (pin "2") (pinfunction "GND_2") (pintype "bidirectional"))
    )
    (net (code "118") (name "Net-(IC2-CAN_H)") (class "Default")
      (node (ref "IC2") (pin "7") (pinfunction "CAN_H_7") (pintype "bidirectional"))
      (node (ref "JP4") (pin "1") (pinfunction "1_1") (pintype "passive"))
    )
    (net (code "119") (name "Net-(IC2-CAN_L)") (class "Default")
      (node (ref "IC2") (pin "6") (pinfunction "CAN_L_6") (pintype "bidirectional"))
      (node (ref "JP4") (pin "3") (pinfunction "3_3") (pintype "passive"))
    )
    (net (code "120") (name "Net-(IC2-RS)") (class "Default")
      (node (ref "IC2") (pin "8") (pinfunction "RS_8") (pintype "bidirectional"))
      (node (ref "R4") (pin "1") (pinfunction "1_1") (pintype "passive"))
    )
    (net (code "121") (name "Net-(IC6-CAN_H)") (class "Default")
      (node (ref "IC6") (pin "7") (pinfunction "CAN_H_7") (pintype "bidirectional"))
      (node (ref "JP5") (pin "1") (pinfunction "1_1") (pintype "passive"))
    )
    (net (code "122") (name "Net-(IC6-CAN_L)") (class "Default")
      (node (ref "IC6") (pin "6") (pinfunction "CAN_L_6") (pintype "bidirectional"))
      (node (ref "JP5") (pin "3") (pinfunction "3_3") (pintype "passive"))
    )
    (net (code "123") (name "Net-(IC6-RS)") (class "Default")
      (node (ref "IC6") (pin "8") (pinfunction "RS_8") (pintype "bidirectional"))
      (node (ref "R7") (pin "1") (pinfunction "1_1") (pintype "passive"))
    )
    (net (code "124") (name "Net-(IC7-CAN_H)") (class "Default")
      (node (ref "IC7") (pin "7") (pinfunction "CAN_H_7") (pintype "bidirectional"))
      (node (ref "JP6") (pin "1") (pinfunction "1_1") (pintype "passive"))
    )
    (net (code "125") (name "Net-(IC7-CAN_L)") (class "Default")
      (node (ref "IC7") (pin "6") (pinfunction "CAN_L_6") (pintype "bidirectional"))
      (node (ref "JP6") (pin "3") (pinfunction "3_3") (pintype "passive"))
    )
    (net (code "126") (name "Net-(IC7-RS)") (class "Default")
      (node (ref "IC7") (pin "8") (pinfunction "RS_8") (pintype "bidirectional"))
      (node (ref "R8") (pin "1") (pinfunction "1_1") (pintype "passive"))
    )
    (net (code "127") (name "Net-(IC8-CAN_H)") (class "Default")
      (node (ref "IC8") (pin "7") (pinfunction "CAN_H_7") (pintype "bidirectional"))
      (node (ref "JP7") (pin "1") (pinfunction "1_1") (pintype "passive"))
    )
    (net (code "128") (name "Net-(IC8-CAN_L)") (class "Default")
      (node (ref "IC8") (pin "6") (pinfunction "CAN_L_6") (pintype "bidirectional"))
      (node (ref "JP7") (pin "3") (pinfunction "3_3") (pintype "passive"))
    )
    (net (code "129") (name "Net-(IC8-RS)") (class "Default")
      (node (ref "IC8") (pin "8") (pinfunction "RS_8") (pintype "bidirectional"))
      (node (ref "R6") (pin "1") (pinfunction "1_1") (pintype "passive"))
    )
    (net (code "130") (name "Net-(IC9-A)") (class "Default")
      (node (ref "IC9") (pin "2") (pinfunction "A_2") (pintype "bidirectional"))
      (node (ref "R17") (pin "2") (pinfunction "2_2") (pintype "passive"))
      (node (ref "R18") (pin "1") (pinfunction "1_1") (pintype "passive"))
    )
    (net (code "131") (name "Net-(IC9-REF)") (class "Default")
      (node (ref "IC9") (pin "1") (pinfunction "REF_1") (pintype "input"))
      (node (ref "R16") (pin "2") (pinfunction "2_2") (pintype "passive"))
      (node (ref "R17") (pin "1") (pinfunction "1_1") (pintype "passive"))
    )
    (net (code "132") (name "Net-(IC10-CAN_H)") (class "Default")
      (node (ref "IC10") (pin "7") (pinfunction "CAN_H_7") (pintype "bidirectional"))
      (node (ref "JP3") (pin "1") (pinfunction "1_1") (pintype "passive"))
    )
    (net (code "133") (name "Net-(IC10-CAN_L)") (class "Default")
      (node (ref "IC10") (pin "6") (pinfunction "CAN_L_6") (pintype "bidirectional"))
      (node (ref "JP3") (pin "3") (pinfunction "3_3") (pintype "passive"))
    )
    (net (code "134") (name "Net-(IC10-RS)") (class "Default")
      (node (ref "IC10") (pin "8") (pinfunction "RS_8") (pintype "bidirectional"))
      (node (ref "R5") (pin "1") (pinfunction "1_1") (pintype "passive"))
    )
    (net (code "135") (name "Net-(IC22-VREF)") (class "Default")
      (node (ref "IC22") (pin "10") (pinfunction "VREF_10") (pintype "bidirectional"))
      (node (ref "R20") (pin "1") (pinfunction "1_1") (pintype "passive"))
    )
    (net (code "136") (name "Net-(JP25-Pad1)") (class "Default")
      (node (ref "JP25") (pin "1") (pinfunction "1_1") (pintype "passive"))
      (node (ref "JP30") (pin "1") (pinfunction "1_1") (pintype "passive"))
    )
    (net (code "137") (name "Net-(JP27-Pad1)") (class "Default")
      (node (ref "JP27") (pin "1") (pinfunction "1_1") (pintype "passive"))
      (node (ref "JP31") (pin "1") (pinfunction "1_1") (pintype "passive"))
    )
    (net (code "138") (name "Net-(JP28-Pad1)") (class "Default")
      (node (ref "JP28") (pin "1") (pinfunction "1_1") (pintype "passive"))
      (node (ref "JP32") (pin "1") (pinfunction "1_1") (pintype "passive"))
    )
    (net (code "139") (name "Net-(JP29-Pad1)") (class "Default")
      (node (ref "JP29") (pin "1") (pinfunction "1_1") (pintype "passive"))
      (node (ref "JP33") (pin "1") (pinfunction "1_1") (pintype "passive"))
    )
    (net (code "140") (name "Net-(JP34-Pad1)") (class "Default")
      (node (ref "JP34") (pin "1") (pinfunction "1_1") (pintype "passive"))
      (node (ref "JP35") (pin "1") (pinfunction "1_1") (pintype "passive"))
    )
    (net (code "141") (name "Net-(JP37-Pad1)") (class "Default")
      (node (ref "JP37") (pin "1") (pinfunction "1_1") (pintype "passive"))
      (node (ref "U$22") (pin "2") (pinfunction "2_2") (pintype "passive"))
    )
    (net (code "142") (name "Net-(LED1-PadA)") (class "Default")
      (node (ref "LED1") (pin "A") (pinfunction "A_A") (pintype "passive"))
      (node (ref "R23") (pin "1") (pinfunction "1_1") (pintype "passive"))
    )
    (net (code "143") (name "Net-(LED2-PadA)") (class "Default")
      (node (ref "LED2") (pin "A") (pinfunction "A_A") (pintype "passive"))
      (node (ref "R2") (pin "1") (pinfunction "1_1") (pintype "passive"))
    )
    (net (code "144") (name "Net-(LED3-PadA)") (class "Default")
      (node (ref "LED3") (pin "A") (pinfunction "A_A") (pintype "passive"))
      (node (ref "R28") (pin "1") (pinfunction "1_1") (pintype "passive"))
    )
    (net (code "145") (name "Net-(LED4-PadA)") (class "Default")
      (node (ref "LED4") (pin "A") (pinfunction "A_A") (pintype "passive"))
      (node (ref "R29") (pin "1") (pinfunction "1_1") (pintype "passive"))
    )
    (net (code "146") (name "Net-(LED5-PadA)") (class "Default")
      (node (ref "LED5") (pin "A") (pinfunction "A_A") (pintype "passive"))
      (node (ref "R30") (pin "1") (pinfunction "1_1") (pintype "passive"))
    )
    (net (code "147") (name "Net-(U$23-P0.7{slash}SCK1)") (class "Default")
      (node (ref "U$23") (pin "5") (pinfunction "P0.7/SCK1_5") (pintype "bidirectional"))
      (node (ref "U$24") (pin "5") (pinfunction "P0.7/SCK1_5") (pintype "bidirectional"))
    )
    (net (code "148") (name "Net-(U$23-P0.8{slash}MISO1)") (class "Default")
      (node (ref "U$23") (pin "7") (pinfunction "P0.8/MISO1_7") (pintype "bidirectional"))
      (node (ref "U$24") (pin "7") (pinfunction "P0.8/MISO1_7") (pintype "bidirectional"))
    )
    (net (code "149") (name "Net-(U$23-P0.9{slash}MOSI1)") (class "Default")
      (node (ref "U$23") (pin "9") (pinfunction "P0.9/MOSI1_9") (pintype "bidirectional"))
      (node (ref "U$24") (pin "9") (pinfunction "P0.9/MOSI1_9") (pintype "bidirectional"))
    )
    (net (code "150") (name "Net-(U$23-P0.15{slash}SCK0)") (class "Default")
      (node (ref "U$23") (pin "26") (pinfunction "P0.15/SCK0_26") (pintype "bidirectional"))
      (node (ref "U$24") (pin "26") (pinfunction "P0.15/SCK0_26") (pintype "bidirectional"))
    )
    (net (code "151") (name "Net-(U$23-P0.17{slash}MISO0)") (class "Default")
      (node (ref "U$23") (pin "28") (pinfunction "P0.17/MISO0_28") (pintype "bidirectional"))
      (node (ref "U$24") (pin "28") (pinfunction "P0.17/MISO0_28") (pintype "bidirectional"))
    )
    (net (code "152") (name "Net-(U$23-P0.18{slash}MOSI0)") (class "Default")
      (node (ref "U$23") (pin "30") (pinfunction "P0.18/MOSI0_30") (pintype "bidirectional"))
      (node (ref "U$24") (pin "30") (pinfunction "P0.18/MOSI0_30") (pintype "bidirectional"))
    )
    (net (code "153") (name "Net-(U$23-P0.26{slash}ADC)") (class "Default")
      (node (ref "U$23") (pin "11") (pinfunction "P0.26/ADC_11") (pintype "bidirectional"))
      (node (ref "U$24") (pin "11") (pinfunction "P0.26/ADC_11") (pintype "bidirectional"))
    )
    (net (code "154") (name "Net-(U$23-P0.29)") (class "Default")
      (node (ref "U$23") (pin "31") (pinfunction "P0.29_31") (pintype "bidirectional"))
      (node (ref "U$24") (pin "31") (pinfunction "P0.29_31") (pintype "bidirectional"))
    )
    (net (code "155") (name "Net-(U$23-P0.30)") (class "Default")
      (node (ref "U$23") (pin "29") (pinfunction "P0.30_29") (pintype "bidirectional"))
      (node (ref "U$24") (pin "29") (pinfunction "P0.30_29") (pintype "bidirectional"))
    )
    (net (code "156") (name "Net-(U$23-P1.19)") (class "Default")
      (node (ref "U$23") (pin "27") (pinfunction "P1.19_27") (pintype "bidirectional"))
      (node (ref "U$24") (pin "27") (pinfunction "P1.19_27") (pintype "bidirectional"))
    )
    (net (code "157") (name "Net-(U$23-P1.20)") (class "Default")
      (node (ref "U$23") (pin "25") (pinfunction "P1.20_25") (pintype "bidirectional"))
      (node (ref "U$24") (pin "25") (pinfunction "P1.20_25") (pintype "bidirectional"))
    )
    (net (code "158") (name "Net-(U$23-P1.22)") (class "Default")
      (node (ref "U$23") (pin "23") (pinfunction "P1.22_23") (pintype "bidirectional"))
      (node (ref "U$24") (pin "23") (pinfunction "P1.22_23") (pintype "bidirectional"))
    )
    (net (code "159") (name "Net-(U$23-P1.23)") (class "Default")
      (node (ref "U$23") (pin "21") (pinfunction "P1.23_21") (pintype "bidirectional"))
      (node (ref "U$24") (pin "21") (pinfunction "P1.23_21") (pintype "bidirectional"))
    )
    (net (code "160") (name "Net-(U$23-P1.28)") (class "Default")
      (node (ref "U$23") (pin "19") (pinfunction "P1.28_19") (pintype "bidirectional"))
      (node (ref "U$24") (pin "19") (pinfunction "P1.28_19") (pintype "bidirectional"))
    )
    (net (code "161") (name "Net-(U$23-P1.29)") (class "Default")
      (node (ref "U$23") (pin "17") (pinfunction "P1.29_17") (pintype "bidirectional"))
      (node (ref "U$24") (pin "17") (pinfunction "P1.29_17") (pintype "bidirectional"))
    )
    (net (code "162") (name "Net-(U$23-P1.30{slash}ADC)") (class "Default")
      (node (ref "U$23") (pin "15") (pinfunction "P1.30/ADC_15") (pintype "bidirectional"))
      (node (ref "U$24") (pin "15") (pinfunction "P1.30/ADC_15") (pintype "bidirectional"))
    )
    (net (code "163") (name "Net-(U$23-P1.31{slash}ADC)") (class "Default")
      (node (ref "U$23") (pin "13") (pinfunction "P1.31/ADC_13") (pintype "bidirectional"))
      (node (ref "U$24") (pin "13") (pinfunction "P1.31/ADC_13") (pintype "bidirectional"))
    )
    (net (code "164") (name "Net-(U$23-P2.0{slash}PWM)") (class "Default")
      (node (ref "U$23") (pin "6") (pinfunction "P2.0/PWM_6") (pintype "bidirectional"))
      (node (ref "U$24") (pin "6") (pinfunction "P2.0/PWM_6") (pintype "bidirectional"))
    )
    (net (code "165") (name "Net-(U$23-P2.1{slash}PWM)") (class "Default")
      (node (ref "U$23") (pin "8") (pinfunction "P2.1/PWM_8") (pintype "bidirectional"))
      (node (ref "U$24") (pin "8") (pinfunction "P2.1/PWM_8") (pintype "bidirectional"))
    )
    (net (code "166") (name "Net-(U$23-P2.2{slash}PWM)") (class "Default")
      (node (ref "U$23") (pin "10") (pinfunction "P2.2/PWM_10") (pintype "bidirectional"))
      (node (ref "U$24") (pin "10") (pinfunction "P2.2/PWM_10") (pintype "bidirectional"))
    )
    (net (code "167") (name "Net-(U$23-P2.3{slash}PWM)") (class "Default")
      (node (ref "U$23") (pin "12") (pinfunction "P2.3/PWM_12") (pintype "bidirectional"))
      (node (ref "U$24") (pin "12") (pinfunction "P2.3/PWM_12") (pintype "bidirectional"))
    )
    (net (code "168") (name "Net-(U$23-P2.4{slash}PWM)") (class "Default")
      (node (ref "U$23") (pin "14") (pinfunction "P2.4/PWM_14") (pintype "bidirectional"))
      (node (ref "U$24") (pin "14") (pinfunction "P2.4/PWM_14") (pintype "bidirectional"))
    )
    (net (code "169") (name "Net-(U$23-P2.5{slash}PWM)") (class "Default")
      (node (ref "U$23") (pin "16") (pinfunction "P2.5/PWM_16") (pintype "bidirectional"))
      (node (ref "U$24") (pin "16") (pinfunction "P2.5/PWM_16") (pintype "bidirectional"))
    )
    (net (code "170") (name "Net-(U$23-P2.6{slash}PWM)") (class "Default")
      (node (ref "U$23") (pin "18") (pinfunction "P2.6/PWM_18") (pintype "bidirectional"))
      (node (ref "U$24") (pin "18") (pinfunction "P2.6/PWM_18") (pintype "bidirectional"))
    )
    (net (code "171") (name "Net-(U$23-P2.7{slash}PWM{slash}CAN2RX)") (class "Default")
      (node (ref "U$23") (pin "20") (pinfunction "P2.7/PWM/CAN2RX_20") (pintype "bidirectional"))
      (node (ref "U$24") (pin "20") (pinfunction "P2.7/PWM/CAN2RX_20") (pintype "bidirectional"))
    )
    (net (code "172") (name "Net-(U$23-P2.8{slash}CAN2TX{slash}TXD2)") (class "Default")
      (node (ref "U$23") (pin "22") (pinfunction "P2.8/CAN2TX/TXD2_22") (pintype "bidirectional"))
      (node (ref "U$24") (pin "22") (pinfunction "P2.8/CAN2TX/TXD2_22") (pintype "bidirectional"))
    )
    (net (code "173") (name "Net-(U$23-P2.9{slash}RXD2)") (class "Default")
      (node (ref "U$23") (pin "24") (pinfunction "P2.9/RXD2_24") (pintype "bidirectional"))
      (node (ref "U$24") (pin "24") (pinfunction "P2.9/RXD2_24") (pintype "bidirectional"))
    )
    (net (code "174") (name "Net-(U$23-P4.28{slash}TXD3)") (class "Default")
      (node (ref "U$23") (pin "3") (pinfunction "P4.28/TXD3_3") (pintype "bidirectional"))
      (node (ref "U$24") (pin "3") (pinfunction "P4.28/TXD3_3") (pintype "bidirectional"))
    )
    (net (code "175") (name "Net-(U$23-P4.29{slash}RXD3)") (class "Default")
      (node (ref "U$23") (pin "1") (pinfunction "P4.29/RXD3_1") (pintype "bidirectional"))
      (node (ref "U$24") (pin "1") (pinfunction "P4.29/RXD3_1") (pintype "bidirectional"))
    )
    (net (code "176") (name "Net-(U$25-P0.0{slash}CAN1RX)") (class "Default")
      (node (ref "U$25") (pin "34") (pinfunction "P0.0/CAN1RX_34") (pintype "bidirectional"))
      (node (ref "U$26") (pin "34") (pinfunction "P0.0/CAN1RX_34") (pintype "bidirectional"))
    )
    (net (code "177") (name "Net-(U$25-P0.1{slash}CAN1TX)") (class "Default")
      (node (ref "U$25") (pin "32") (pinfunction "P0.1/CAN1TX_32") (pintype "bidirectional"))
      (node (ref "U$26") (pin "32") (pinfunction "P0.1/CAN1TX_32") (pintype "bidirectional"))
    )
    (net (code "178") (name "Net-(U$25-P0.15{slash}SCK0)") (class "Default")
      (node (ref "U$25") (pin "26") (pinfunction "P0.15/SCK0_26") (pintype "bidirectional"))
      (node (ref "U$26") (pin "26") (pinfunction "P0.15/SCK0_26") (pintype "bidirectional"))
    )
    (net (code "179") (name "Net-(U$25-P0.17{slash}MISO0)") (class "Default")
      (node (ref "U$25") (pin "28") (pinfunction "P0.17/MISO0_28") (pintype "bidirectional"))
      (node (ref "U$26") (pin "28") (pinfunction "P0.17/MISO0_28") (pintype "bidirectional"))
    )
    (net (code "180") (name "Net-(U$25-P0.18{slash}MOSI0)") (class "Default")
      (node (ref "U$25") (pin "30") (pinfunction "P0.18/MOSI0_30") (pintype "bidirectional"))
      (node (ref "U$26") (pin "30") (pinfunction "P0.18/MOSI0_30") (pintype "bidirectional"))
    )
    (net (code "181") (name "Net-(U$25-P0.29)") (class "Default")
      (node (ref "U$25") (pin "31") (pinfunction "P0.29_31") (pintype "bidirectional"))
      (node (ref "U$26") (pin "31") (pinfunction "P0.29_31") (pintype "bidirectional"))
    )
    (net (code "182") (name "Net-(U$25-P0.30)") (class "Default")
      (node (ref "U$25") (pin "29") (pinfunction "P0.30_29") (pintype "bidirectional"))
      (node (ref "U$26") (pin "29") (pinfunction "P0.30_29") (pintype "bidirectional"))
    )
    (net (code "183") (name "Net-(U$25-P1.28)") (class "Default")
      (node (ref "U$25") (pin "19") (pinfunction "P1.28_19") (pintype "bidirectional"))
      (node (ref "U$26") (pin "19") (pinfunction "P1.28_19") (pintype "bidirectional"))
    )
    (net (code "184") (name "Net-(U$25-P1.30{slash}ADC)") (class "Default")
      (node (ref "U$25") (pin "15") (pinfunction "P1.30/ADC_15") (pintype "bidirectional"))
      (node (ref "U$26") (pin "15") (pinfunction "P1.30/ADC_15") (pintype "bidirectional"))
    )
    (net (code "185") (name "Net-(U$25-P1.31{slash}ADC)") (class "Default")
      (node (ref "U$25") (pin "13") (pinfunction "P1.31/ADC_13") (pintype "bidirectional"))
      (node (ref "U$26") (pin "13") (pinfunction "P1.31/ADC_13") (pintype "bidirectional"))
    )
    (net (code "186") (name "Net-(U$25-P2.2{slash}PWM)") (class "Default")
      (node (ref "U$25") (pin "10") (pinfunction "P2.2/PWM_10") (pintype "bidirectional"))
      (node (ref "U$26") (pin "10") (pinfunction "P2.2/PWM_10") (pintype "bidirectional"))
    )
    (net (code "187") (name "Net-(U$25-P2.9{slash}RXD2)") (class "Default")
      (node (ref "U$25") (pin "24") (pinfunction "P2.9/RXD2_24") (pintype "bidirectional"))
      (node (ref "U$26") (pin "24") (pinfunction "P2.9/RXD2_24") (pintype "bidirectional"))
    )
    (net (code "188") (name "Net-(U$25-P4.28{slash}TXD3)") (class "Default")
      (node (ref "U$25") (pin "3") (pinfunction "P4.28/TXD3_3") (pintype "bidirectional"))
      (node (ref "U$26") (pin "3") (pinfunction "P4.28/TXD3_3") (pintype "bidirectional"))
    )
    (net (code "189") (name "Net-(U$25-P4.29{slash}RXD3)") (class "Default")
      (node (ref "U$25") (pin "1") (pinfunction "P4.29/RXD3_1") (pintype "bidirectional"))
      (node (ref "U$26") (pin "1") (pinfunction "P4.29/RXD3_1") (pintype "bidirectional"))
    )
    (net (code "190") (name "Net-(U$27-P0.7{slash}SCK1)") (class "Default")
      (node (ref "U$27") (pin "5") (pinfunction "P0.7/SCK1_5") (pintype "bidirectional"))
      (node (ref "U$30") (pin "5") (pinfunction "P0.7/SCK1_5") (pintype "bidirectional"))
    )
    (net (code "191") (name "Net-(U$27-P0.8{slash}MISO1)") (class "Default")
      (node (ref "U$27") (pin "7") (pinfunction "P0.8/MISO1_7") (pintype "bidirectional"))
      (node (ref "U$30") (pin "7") (pinfunction "P0.8/MISO1_7") (pintype "bidirectional"))
    )
    (net (code "192") (name "Net-(U$27-P0.9{slash}MOSI1)") (class "Default")
      (node (ref "U$27") (pin "9") (pinfunction "P0.9/MOSI1_9") (pintype "bidirectional"))
      (node (ref "U$30") (pin "9") (pinfunction "P0.9/MOSI1_9") (pintype "bidirectional"))
    )
    (net (code "193") (name "Net-(U$27-P0.15{slash}SCK0)") (class "Default")
      (node (ref "U$27") (pin "26") (pinfunction "P0.15/SCK0_26") (pintype "bidirectional"))
      (node (ref "U$30") (pin "26") (pinfunction "P0.15/SCK0_26") (pintype "bidirectional"))
    )
    (net (code "194") (name "Net-(U$27-P0.17{slash}MISO0)") (class "Default")
      (node (ref "U$27") (pin "28") (pinfunction "P0.17/MISO0_28") (pintype "bidirectional"))
      (node (ref "U$30") (pin "28") (pinfunction "P0.17/MISO0_28") (pintype "bidirectional"))
    )
    (net (code "195") (name "Net-(U$27-P0.18{slash}MOSI0)") (class "Default")
      (node (ref "U$27") (pin "30") (pinfunction "P0.18/MOSI0_30") (pintype "bidirectional"))
      (node (ref "U$30") (pin "30") (pinfunction "P0.18/MOSI0_30") (pintype "bidirectional"))
    )
    (net (code "196") (name "Net-(U$27-P0.26{slash}ADC)") (class "Default")
      (node (ref "U$27") (pin "11") (pinfunction "P0.26/ADC_11") (pintype "bidirectional"))
      (node (ref "U$30") (pin "11") (pinfunction "P0.26/ADC_11") (pintype "bidirectional"))
    )
    (net (code "197") (name "Net-(U$27-P0.29)") (class "Default")
      (node (ref "U$27") (pin "31") (pinfunction "P0.29_31") (pintype "bidirectional"))
      (node (ref "U$30") (pin "31") (pinfunction "P0.29_31") (pintype "bidirectional"))
    )
    (net (code "198") (name "Net-(U$27-P0.30)") (class "Default")
      (node (ref "U$27") (pin "29") (pinfunction "P0.30_29") (pintype "bidirectional"))
      (node (ref "U$30") (pin "29") (pinfunction "P0.30_29") (pintype "bidirectional"))
    )
    (net (code "199") (name "Net-(U$27-P1.19)") (class "Default")
      (node (ref "U$27") (pin "27") (pinfunction "P1.19_27") (pintype "bidirectional"))
      (node (ref "U$30") (pin "27") (pinfunction "P1.19_27") (pintype "bidirectional"))
    )
    (net (code "200") (name "Net-(U$27-P1.20)") (class "Default")
      (node (ref "U$27") (pin "25") (pinfunction "P1.20_25") (pintype "bidirectional"))
      (node (ref "U$30") (pin "25") (pinfunction "P1.20_25") (pintype "bidirectional"))
    )
    (net (code "201") (name "Net-(U$27-P1.22)") (class "Default")
      (node (ref "U$27") (pin "23") (pinfunction "P1.22_23") (pintype "bidirectional"))
      (node (ref "U$30") (pin "23") (pinfunction "P1.22_23") (pintype "bidirectional"))
    )
    (net (code "202") (name "Net-(U$27-P1.23)") (class "Default")
      (node (ref "U$27") (pin "21") (pinfunction "P1.23_21") (pintype "bidirectional"))
      (node (ref "U$30") (pin "21") (pinfunction "P1.23_21") (pintype "bidirectional"))
    )
    (net (code "203") (name "Net-(U$27-P1.30{slash}ADC)") (class "Default")
      (node (ref "U$27") (pin "15") (pinfunction "P1.30/ADC_15") (pintype "bidirectional"))
      (node (ref "U$30") (pin "15") (pinfunction "P1.30/ADC_15") (pintype "bidirectional"))
    )
    (net (code "204") (name "Net-(U$27-P1.31{slash}ADC)") (class "Default")
      (node (ref "U$27") (pin "13") (pinfunction "P1.31/ADC_13") (pintype "bidirectional"))
      (node (ref "U$30") (pin "13") (pinfunction "P1.31/ADC_13") (pintype "bidirectional"))
    )
    (net (code "205") (name "Net-(U$27-P2.2{slash}PWM)") (class "Default")
      (node (ref "U$27") (pin "10") (pinfunction "P2.2/PWM_10") (pintype "bidirectional"))
      (node (ref "U$30") (pin "10") (pinfunction "P2.2/PWM_10") (pintype "bidirectional"))
    )
    (net (code "206") (name "Net-(U$27-P2.3{slash}PWM)") (class "Default")
      (node (ref "U$27") (pin "12") (pinfunction "P2.3/PWM_12") (pintype "bidirectional"))
      (node (ref "U$30") (pin "12") (pinfunction "P2.3/PWM_12") (pintype "bidirectional"))
    )
    (net (code "207") (name "Net-(U$27-P2.4{slash}PWM)") (class "Default")
      (node (ref "U$27") (pin "14") (pinfunction "P2.4/PWM_14") (pintype "bidirectional"))
      (node (ref "U$30") (pin "14") (pinfunction "P2.4/PWM_14") (pintype "bidirectional"))
    )
    (net (code "208") (name "Net-(U$27-P2.5{slash}PWM)") (class "Default")
      (node (ref "U$27") (pin "16") (pinfunction "P2.5/PWM_16") (pintype "bidirectional"))
      (node (ref "U$30") (pin "16") (pinfunction "P2.5/PWM_16") (pintype "bidirectional"))
    )
    (net (code "209") (name "Net-(U$27-P2.6{slash}PWM)") (class "Default")
      (node (ref "U$27") (pin "18") (pinfunction "P2.6/PWM_18") (pintype "bidirectional"))
      (node (ref "U$30") (pin "18") (pinfunction "P2.6/PWM_18") (pintype "bidirectional"))
    )
    (net (code "210") (name "Net-(U$27-P2.7{slash}PWM{slash}CAN2RX)") (class "Default")
      (node (ref "U$27") (pin "20") (pinfunction "P2.7/PWM/CAN2RX_20") (pintype "bidirectional"))
      (node (ref "U$30") (pin "20") (pinfunction "P2.7/PWM/CAN2RX_20") (pintype "bidirectional"))
    )
    (net (code "211") (name "Net-(U$27-P4.28{slash}TXD3)") (class "Default")
      (node (ref "U$27") (pin "3") (pinfunction "P4.28/TXD3_3") (pintype "bidirectional"))
      (node (ref "U$30") (pin "3") (pinfunction "P4.28/TXD3_3") (pintype "bidirectional"))
    )
    (net (code "212") (name "Net-(U$27-P4.29{slash}RXD3)") (class "Default")
      (node (ref "U$27") (pin "1") (pinfunction "P4.29/RXD3_1") (pintype "bidirectional"))
      (node (ref "U$30") (pin "1") (pinfunction "P4.29/RXD3_1") (pintype "bidirectional"))
    )
    (net (code "213") (name "Net-(U$28-P0.7{slash}SCK1)") (class "Default")
      (node (ref "U$28") (pin "5") (pinfunction "P0.7/SCK1_5") (pintype "bidirectional"))
      (node (ref "U$29") (pin "5") (pinfunction "P0.7/SCK1_5") (pintype "bidirectional"))
    )
    (net (code "214") (name "Net-(U$28-P0.8{slash}MISO1)") (class "Default")
      (node (ref "U$28") (pin "7") (pinfunction "P0.8/MISO1_7") (pintype "bidirectional"))
      (node (ref "U$29") (pin "7") (pinfunction "P0.8/MISO1_7") (pintype "bidirectional"))
    )
    (net (code "215") (name "Net-(U$28-P0.9{slash}MOSI1)") (class "Default")
      (node (ref "U$28") (pin "9") (pinfunction "P0.9/MOSI1_9") (pintype "bidirectional"))
      (node (ref "U$29") (pin "9") (pinfunction "P0.9/MOSI1_9") (pintype "bidirectional"))
    )
    (net (code "216") (name "Net-(U$28-P0.15{slash}SCK0)") (class "Default")
      (node (ref "U$28") (pin "26") (pinfunction "P0.15/SCK0_26") (pintype "bidirectional"))
      (node (ref "U$29") (pin "26") (pinfunction "P0.15/SCK0_26") (pintype "bidirectional"))
    )
    (net (code "217") (name "Net-(U$28-P0.17{slash}MISO0)") (class "Default")
      (node (ref "U$28") (pin "28") (pinfunction "P0.17/MISO0_28") (pintype "bidirectional"))
      (node (ref "U$29") (pin "28") (pinfunction "P0.17/MISO0_28") (pintype "bidirectional"))
    )
    (net (code "218") (name "Net-(U$28-P0.18{slash}MOSI0)") (class "Default")
      (node (ref "U$28") (pin "30") (pinfunction "P0.18/MOSI0_30") (pintype "bidirectional"))
      (node (ref "U$29") (pin "30") (pinfunction "P0.18/MOSI0_30") (pintype "bidirectional"))
    )
    (net (code "219") (name "Net-(U$28-P0.26{slash}ADC)") (class "Default")
      (node (ref "U$28") (pin "11") (pinfunction "P0.26/ADC_11") (pintype "bidirectional"))
      (node (ref "U$29") (pin "11") (pinfunction "P0.26/ADC_11") (pintype "bidirectional"))
    )
    (net (code "220") (name "Net-(U$28-P0.29)") (class "Default")
      (node (ref "U$28") (pin "31") (pinfunction "P0.29_31") (pintype "bidirectional"))
      (node (ref "U$29") (pin "31") (pinfunction "P0.29_31") (pintype "bidirectional"))
    )
    (net (code "221") (name "Net-(U$28-P0.30)") (class "Default")
      (node (ref "U$28") (pin "29") (pinfunction "P0.30_29") (pintype "bidirectional"))
      (node (ref "U$29") (pin "29") (pinfunction "P0.30_29") (pintype "bidirectional"))
    )
    (net (code "222") (name "Net-(U$28-P1.19)") (class "Default")
      (node (ref "U$28") (pin "27") (pinfunction "P1.19_27") (pintype "bidirectional"))
      (node (ref "U$29") (pin "27") (pinfunction "P1.19_27") (pintype "bidirectional"))
    )
    (net (code "223") (name "Net-(U$28-P1.20)") (class "Default")
      (node (ref "U$28") (pin "25") (pinfunction "P1.20_25") (pintype "bidirectional"))
      (node (ref "U$29") (pin "25") (pinfunction "P1.20_25") (pintype "bidirectional"))
    )
    (net (code "224") (name "Net-(U$28-P1.22)") (class "Default")
      (node (ref "U$28") (pin "23") (pinfunction "P1.22_23") (pintype "bidirectional"))
      (node (ref "U$29") (pin "23") (pinfunction "P1.22_23") (pintype "bidirectional"))
    )
    (net (code "225") (name "Net-(U$28-P1.23)") (class "Default")
      (node (ref "U$28") (pin "21") (pinfunction "P1.23_21") (pintype "bidirectional"))
      (node (ref "U$29") (pin "21") (pinfunction "P1.23_21") (pintype "bidirectional"))
    )
    (net (code "226") (name "Net-(U$28-P1.28)") (class "Default")
      (node (ref "U$28") (pin "19") (pinfunction "P1.28_19") (pintype "bidirectional"))
      (node (ref "U$29") (pin "19") (pinfunction "P1.28_19") (pintype "bidirectional"))
    )
    (net (code "227") (name "Net-(U$28-P1.29)") (class "Default")
      (node (ref "U$28") (pin "17") (pinfunction "P1.29_17") (pintype "bidirectional"))
      (node (ref "U$29") (pin "17") (pinfunction "P1.29_17") (pintype "bidirectional"))
    )
    (net (code "228") (name "Net-(U$28-P1.30{slash}ADC)") (class "Default")
      (node (ref "U$28") (pin "15") (pinfunction "P1.30/ADC_15") (pintype "bidirectional"))
      (node (ref "U$29") (pin "15") (pinfunction "P1.30/ADC_15") (pintype "bidirectional"))
    )
    (net (code "229") (name "Net-(U$28-P1.31{slash}ADC)") (class "Default")
      (node (ref "U$28") (pin "13") (pinfunction "P1.31/ADC_13") (pintype "bidirectional"))
      (node (ref "U$29") (pin "13") (pinfunction "P1.31/ADC_13") (pintype "bidirectional"))
    )
    (net (code "230") (name "Net-(U$28-P2.0{slash}PWM)") (class "Default")
      (node (ref "U$28") (pin "6") (pinfunction "P2.0/PWM_6") (pintype "bidirectional"))
      (node (ref "U$29") (pin "6") (pinfunction "P2.0/PWM_6") (pintype "bidirectional"))
    )
    (net (code "231") (name "Net-(U$28-P2.1{slash}PWM)") (class "Default")
      (node (ref "U$28") (pin "8") (pinfunction "P2.1/PWM_8") (pintype "bidirectional"))
      (node (ref "U$29") (pin "8") (pinfunction "P2.1/PWM_8") (pintype "bidirectional"))
    )
    (net (code "232") (name "Net-(U$28-P2.2{slash}PWM)") (class "Default")
      (node (ref "U$28") (pin "10") (pinfunction "P2.2/PWM_10") (pintype "bidirectional"))
      (node (ref "U$29") (pin "10") (pinfunction "P2.2/PWM_10") (pintype "bidirectional"))
    )
    (net (code "233") (name "Net-(U$28-P2.3{slash}PWM)") (class "Default")
      (node (ref "U$28") (pin "12") (pinfunction "P2.3/PWM_12") (pintype "bidirectional"))
      (node (ref "U$29") (pin "12") (pinfunction "P2.3/PWM_12") (pintype "bidirectional"))
    )
    (net (code "234") (name "Net-(U$28-P2.4{slash}PWM)") (class "Default")
      (node (ref "U$28") (pin "14") (pinfunction "P2.4/PWM_14") (pintype "bidirectional"))
      (node (ref "U$29") (pin "14") (pinfunction "P2.4/PWM_14") (pintype "bidirectional"))
    )
    (net (code "235") (name "Net-(U$28-P2.5{slash}PWM)") (class "Default")
      (node (ref "U$28") (pin "16") (pinfunction "P2.5/PWM_16") (pintype "bidirectional"))
      (node (ref "U$29") (pin "16") (pinfunction "P2.5/PWM_16") (pintype "bidirectional"))
    )
    (net (code "236") (name "Net-(U$28-P2.6{slash}PWM)") (class "Default")
      (node (ref "U$28") (pin "18") (pinfunction "P2.6/PWM_18") (pintype "bidirectional"))
      (node (ref "U$29") (pin "18") (pinfunction "P2.6/PWM_18") (pintype "bidirectional"))
    )
    (net (code "237") (name "Net-(U$28-P2.7{slash}PWM{slash}CAN2RX)") (class "Default")
      (node (ref "U$28") (pin "20") (pinfunction "P2.7/PWM/CAN2RX_20") (pintype "bidirectional"))
      (node (ref "U$29") (pin "20") (pinfunction "P2.7/PWM/CAN2RX_20") (pintype "bidirectional"))
    )
    (net (code "238") (name "Net-(U$28-P2.8{slash}CAN2TX{slash}TXD2)") (class "Default")
      (node (ref "U$28") (pin "22") (pinfunction "P2.8/CAN2TX/TXD2_22") (pintype "bidirectional"))
      (node (ref "U$29") (pin "22") (pinfunction "P2.8/CAN2TX/TXD2_22") (pintype "bidirectional"))
    )
    (net (code "239") (name "Net-(U$28-P2.9{slash}RXD2)") (class "Default")
      (node (ref "U$28") (pin "24") (pinfunction "P2.9/RXD2_24") (pintype "bidirectional"))
      (node (ref "U$29") (pin "24") (pinfunction "P2.9/RXD2_24") (pintype "bidirectional"))
    )
    (net (code "240") (name "VCC") (class "Default")
      (node (ref "C1") (pin "1") (pinfunction "1_1") (pintype "passive"))
      (node (ref "C2") (pin "1") (pinfunction "1_1") (pintype "passive"))
      (node (ref "C20") (pin "1") (pinfunction "1_1") (pintype "passive"))
      (node (ref "C23") (pin "+") (pinfunction "+_+") (pintype "passive"))
      (node (ref "C24") (pin "+") (pinfunction "+_+") (pintype "passive"))
      (node (ref "C25") (pin "+") (pinfunction "+_+") (pintype "passive"))
      (node (ref "C4") (pin "1") (pinfunction "1_1") (pintype "passive"))
      (node (ref "IC1") (pin "16") (pinfunction "VCC_16") (pintype "power_in"))
      (node (ref "IC21") (pin "2") (pinfunction "IN_2") (pintype "bidirectional"))
      (node (ref "IC23") (pin "2") (pinfunction "VCC_2") (pintype "power_in"))
      (node (ref "IC4") (pin "16") (pinfunction "VCC_16") (pintype "power_in"))
      (node (ref "JP25") (pin "2") (pinfunction "2_2") (pintype "passive"))
      (node (ref "JP27") (pin "2") (pinfunction "2_2") (pintype "passive"))
      (node (ref "JP28") (pin "2") (pinfunction "2_2") (pintype "passive"))
      (node (ref "JP29") (pin "2") (pinfunction "2_2") (pintype "passive"))
      (node (ref "JP35") (pin "2") (pinfunction "2_2") (pintype "passive"))
      (node (ref "R2") (pin "2") (pinfunction "2_2") (pintype "passive"))
      (node (ref "R23") (pin "2") (pinfunction "2_2") (pintype "passive"))
      (node (ref "R24") (pin "1") (pinfunction "1_1") (pintype "passive"))
      (node (ref "R25") (pin "1") (pinfunction "1_1") (pintype "passive"))
      (node (ref "R26") (pin "1") (pinfunction "1_1") (pintype "passive"))
      (node (ref "R27") (pin "1") (pinfunction "1_1") (pintype "passive"))
      (node (ref "R28") (pin "2") (pinfunction "2_2") (pintype "passive"))
      (node (ref "U$22") (pin "1") (pinfunction "1_1") (pintype "passive"))
    )
    (net (code "241") (name "unconnected-(IC2-VREF-Pad5)") (class "Default")
      (node (ref "IC2") (pin "5") (pinfunction "VREF_5") (pintype "bidirectional"))
    )
    (net (code "242") (name "unconnected-(IC6-VREF-Pad5)") (class "Default")
      (node (ref "IC6") (pin "5") (pinfunction "VREF_5") (pintype "bidirectional"))
    )
    (net (code "243") (name "unconnected-(IC7-VREF-Pad5)") (class "Default")
      (node (ref "IC7") (pin "5") (pinfunction "VREF_5") (pintype "bidirectional"))
    )
    (net (code "244") (name "unconnected-(IC8-VREF-Pad5)") (class "Default")
      (node (ref "IC8") (pin "5") (pinfunction "VREF_5") (pintype "bidirectional"))
    )
    (net (code "245") (name "unconnected-(IC10-VREF-Pad5)") (class "Default")
      (node (ref "IC10") (pin "5") (pinfunction "VREF_5") (pintype "bidirectional"))
    )
    (net (code "246") (name "unconnected-(IC22-3V3OUT-Pad2)") (class "Default")
      (node (ref "IC22") (pin "2") (pinfunction "3V3OUT_2") (pintype "bidirectional"))
    )
    (net (code "247") (name "unconnected-(IC22-SLP#-Pad5)") (class "Default")
      (node (ref "IC22") (pin "5") (pinfunction "SLP#_5") (pintype "bidirectional"))
    )
    (net (code "248") (name "unconnected-(IC22-VM-Pad1)") (class "Default")
      (node (ref "IC22") (pin "1") (pinfunction "VM_1") (pintype "bidirectional"))
    )
    (net (code "249") (name "unconnected-(IMU_MDL-AD0{slash}SDO-PadP10)") (class "Default")
      (node (ref "IMU_MDL") (pin "P10") (pinfunction "AD0/SDO_P10") (pintype "bidirectional"))
    )
    (net (code "250") (name "unconnected-(IMU_MDL-AUXCL-PadP7)") (class "Default")
      (node (ref "IMU_MDL") (pin "P7") (pinfunction "AUXCL_P7") (pintype "bidirectional"))
    )
    (net (code "251") (name "unconnected-(IMU_MDL-AUXDA-PadP5)") (class "Default")
      (node (ref "IMU_MDL") (pin "P5") (pinfunction "AUXDA_P5") (pintype "bidirectional"))
    )
    (net (code "252") (name "unconnected-(IMU_MDL-CS#-PadP9)") (class "Default")
      (node (ref "IMU_MDL") (pin "P9") (pinfunction "CS#_P9") (pintype "bidirectional"))
    )
    (net (code "253") (name "unconnected-(IMU_MDL-FSYNC-PadP6)") (class "Default")
      (node (ref "IMU_MDL") (pin "P6") (pinfunction "FSYNC_P6") (pintype "bidirectional"))
    )
    (net (code "254") (name "unconnected-(IMU_MDL-INT-PadP8)") (class "Default")
      (node (ref "IMU_MDL") (pin "P8") (pinfunction "INT_P8") (pintype "bidirectional"))
    )
    (net (code "255") (name "unconnected-(IMU_MDL-VDDIO-PadP11)") (class "Default")
      (node (ref "IMU_MDL") (pin "P11") (pinfunction "VDDIO_P11") (pintype "bidirectional"))
    )
    (net (code "256") (name "unconnected-(JP1-Pad4)") (class "Default")
      (node (ref "JP1") (pin "4") (pinfunction "4_4") (pintype "passive"))
    )
    (net (code "257") (name "unconnected-(JP10-Pad1)") (class "Default")
      (node (ref "JP10") (pin "1") (pinfunction "1_1") (pintype "passive"))
    )
    (net (code "258") (name "unconnected-(JP21-Pad6)") (class "Default")
      (node (ref "JP21") (pin "6") (pinfunction "6_6") (pintype "passive"))
    )
    (net (code "259") (name "unconnected-(JP22-Pad3)") (class "Default")
      (node (ref "JP22") (pin "3") (pinfunction "3_3") (pintype "passive"))
    )
    (net (code "260") (name "unconnected-(JP22-Pad5)") (class "Default")
      (node (ref "JP22") (pin "5") (pinfunction "5_5") (pintype "passive"))
    )
    (net (code "261") (name "unconnected-(JP22-Pad7)") (class "Default")
      (node (ref "JP22") (pin "7") (pinfunction "7_7") (pintype "passive"))
    )
    (net (code "262") (name "unconnected-(JP24-Pad1)") (class "Default")
      (node (ref "JP24") (pin "1") (pinfunction "1_1") (pintype "passive"))
    )
    (net (code "263") (name "unconnected-(JP24-Pad2)") (class "Default")
      (node (ref "JP24") (pin "2") (pinfunction "2_2") (pintype "passive"))
    )
    (net (code "264") (name "unconnected-(JP24-Pad3)") (class "Default")
      (node (ref "JP24") (pin "3") (pinfunction "3_3") (pintype "passive"))
    )
    (net (code "265") (name "unconnected-(JP24-Pad4)") (class "Default")
      (node (ref "JP24") (pin "4") (pinfunction "4_4") (pintype "passive"))
    )
    (net (code "266") (name "unconnected-(JP24-Pad5)") (class "Default")
      (node (ref "JP24") (pin "5") (pinfunction "5_5") (pintype "passive"))
    )
    (net (code "267") (name "unconnected-(JP24-Pad6)") (class "Default")
      (node (ref "JP24") (pin "6") (pinfunction "6_6") (pintype "passive"))
    )
    (net (code "268") (name "unconnected-(JP24-Pad9)") (class "Default")
      (node (ref "JP24") (pin "9") (pinfunction "9_9") (pintype "passive"))
    )
    (net (code "269") (name "unconnected-(JP24-Pad10)") (class "Default")
      (node (ref "JP24") (pin "10") (pinfunction "10_10") (pintype "passive"))
    )
    (net (code "270") (name "unconnected-(U$13-<FIX-PadP4)") (class "Default")
      (node (ref "U$13") (pin "P4") (pinfunction "<FIX_P4") (pintype "bidirectional"))
    )
    (net (code "271") (name "unconnected-(U$13-<PPS-PadP9)") (class "Default")
      (node (ref "U$13") (pin "P9") (pinfunction "<PPS_P9") (pintype "bidirectional"))
    )
    (net (code "272") (name "unconnected-(U$13->EN-PadP2)") (class "Default")
      (node (ref "U$13") (pin "P2") (pinfunction ">EN_P2") (pintype "bidirectional"))
    )
    (net (code "273") (name "unconnected-(U$13->VIN-PadP8)") (class "Default")
      (node (ref "U$13") (pin "P8") (pinfunction ">VIN_P8") (pintype "bidirectional"))
    )
    (net (code "274") (name "unconnected-(U$13-VBAT-PadP3)") (class "Default")
      (node (ref "U$13") (pin "P3") (pinfunction "VBAT_P3") (pintype "bidirectional"))
    )
  )
)
